# BlueBus.net
KiCad netlist of a schematic drawn in EAGLE
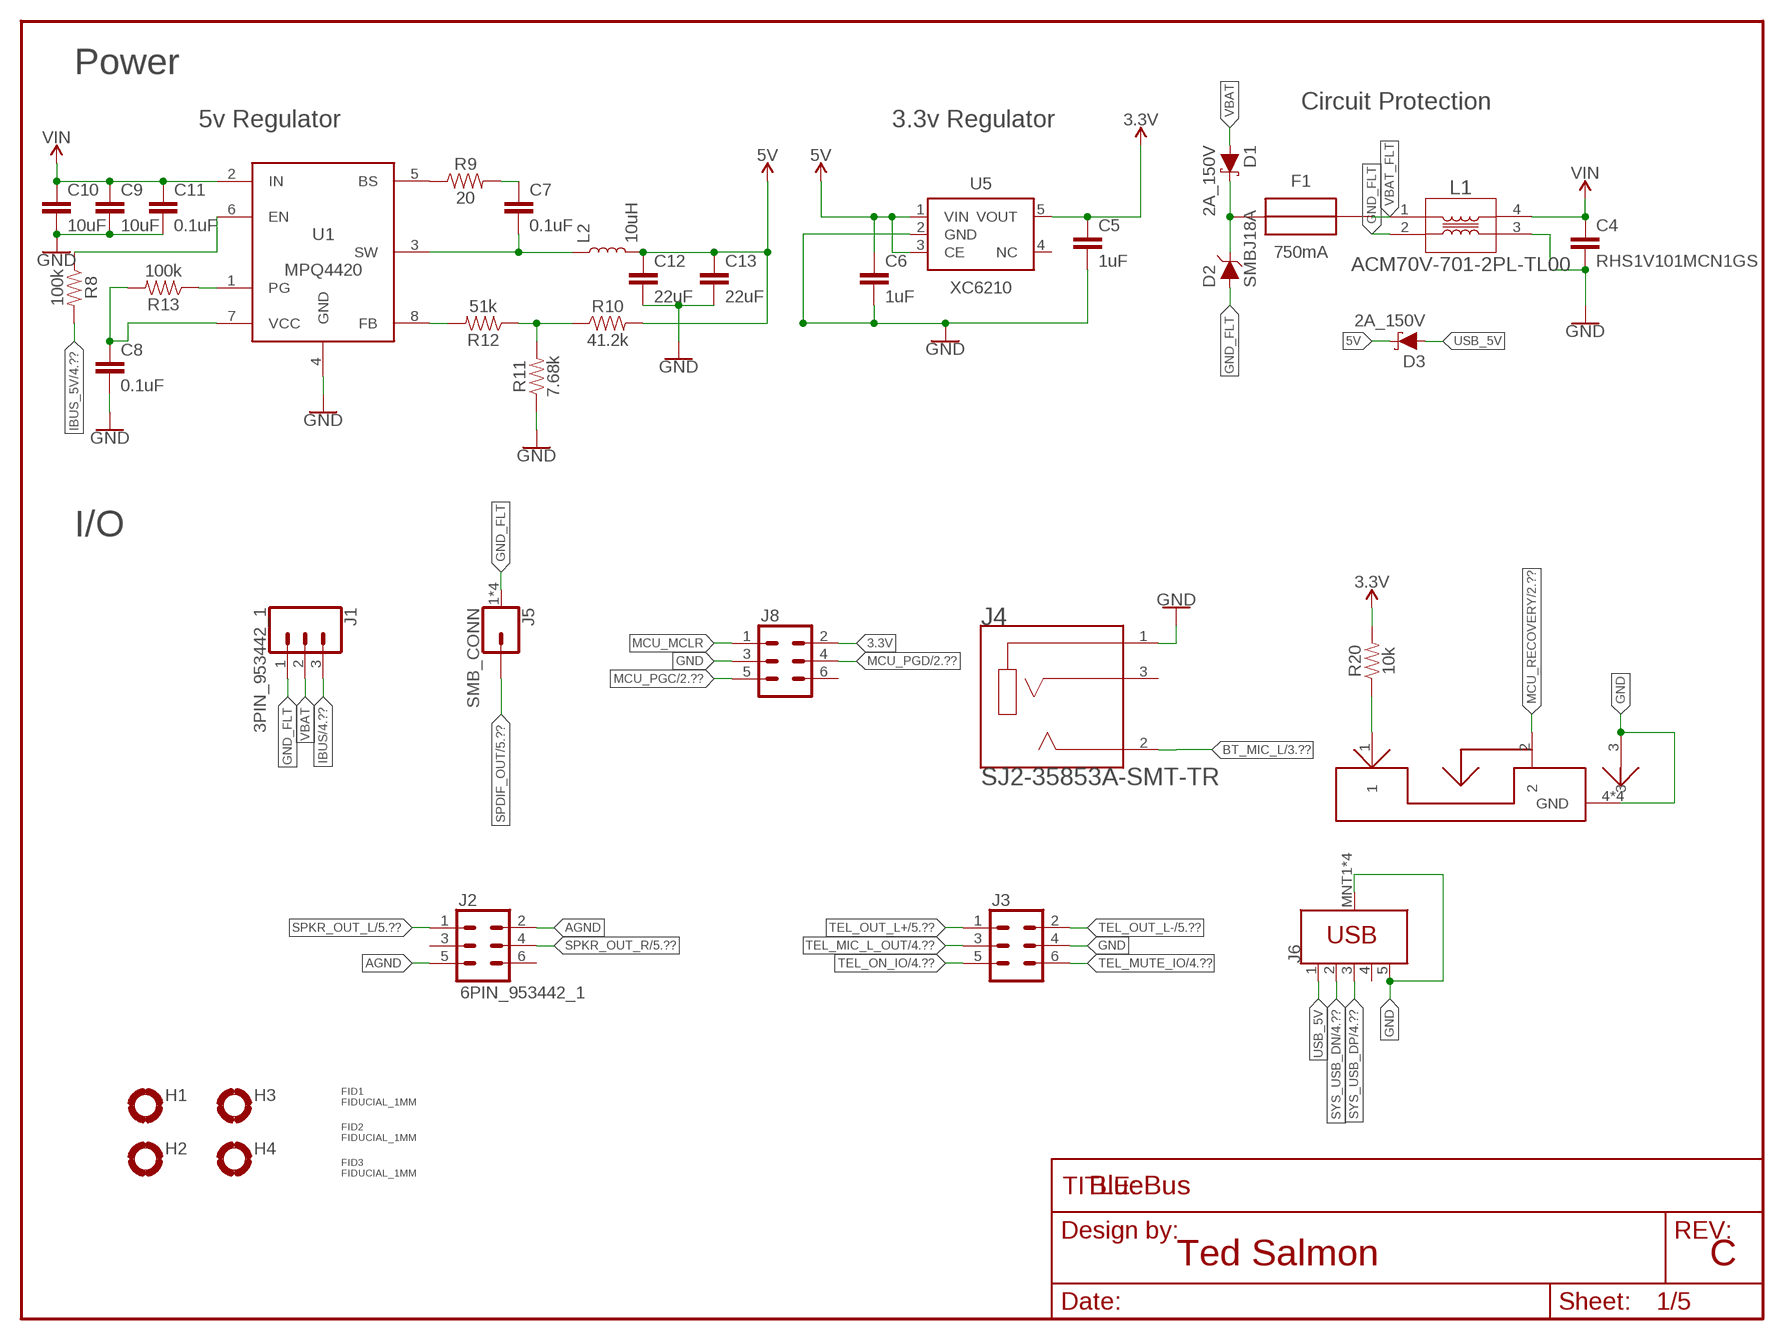
[diagram p0: schematic, sheet 1]
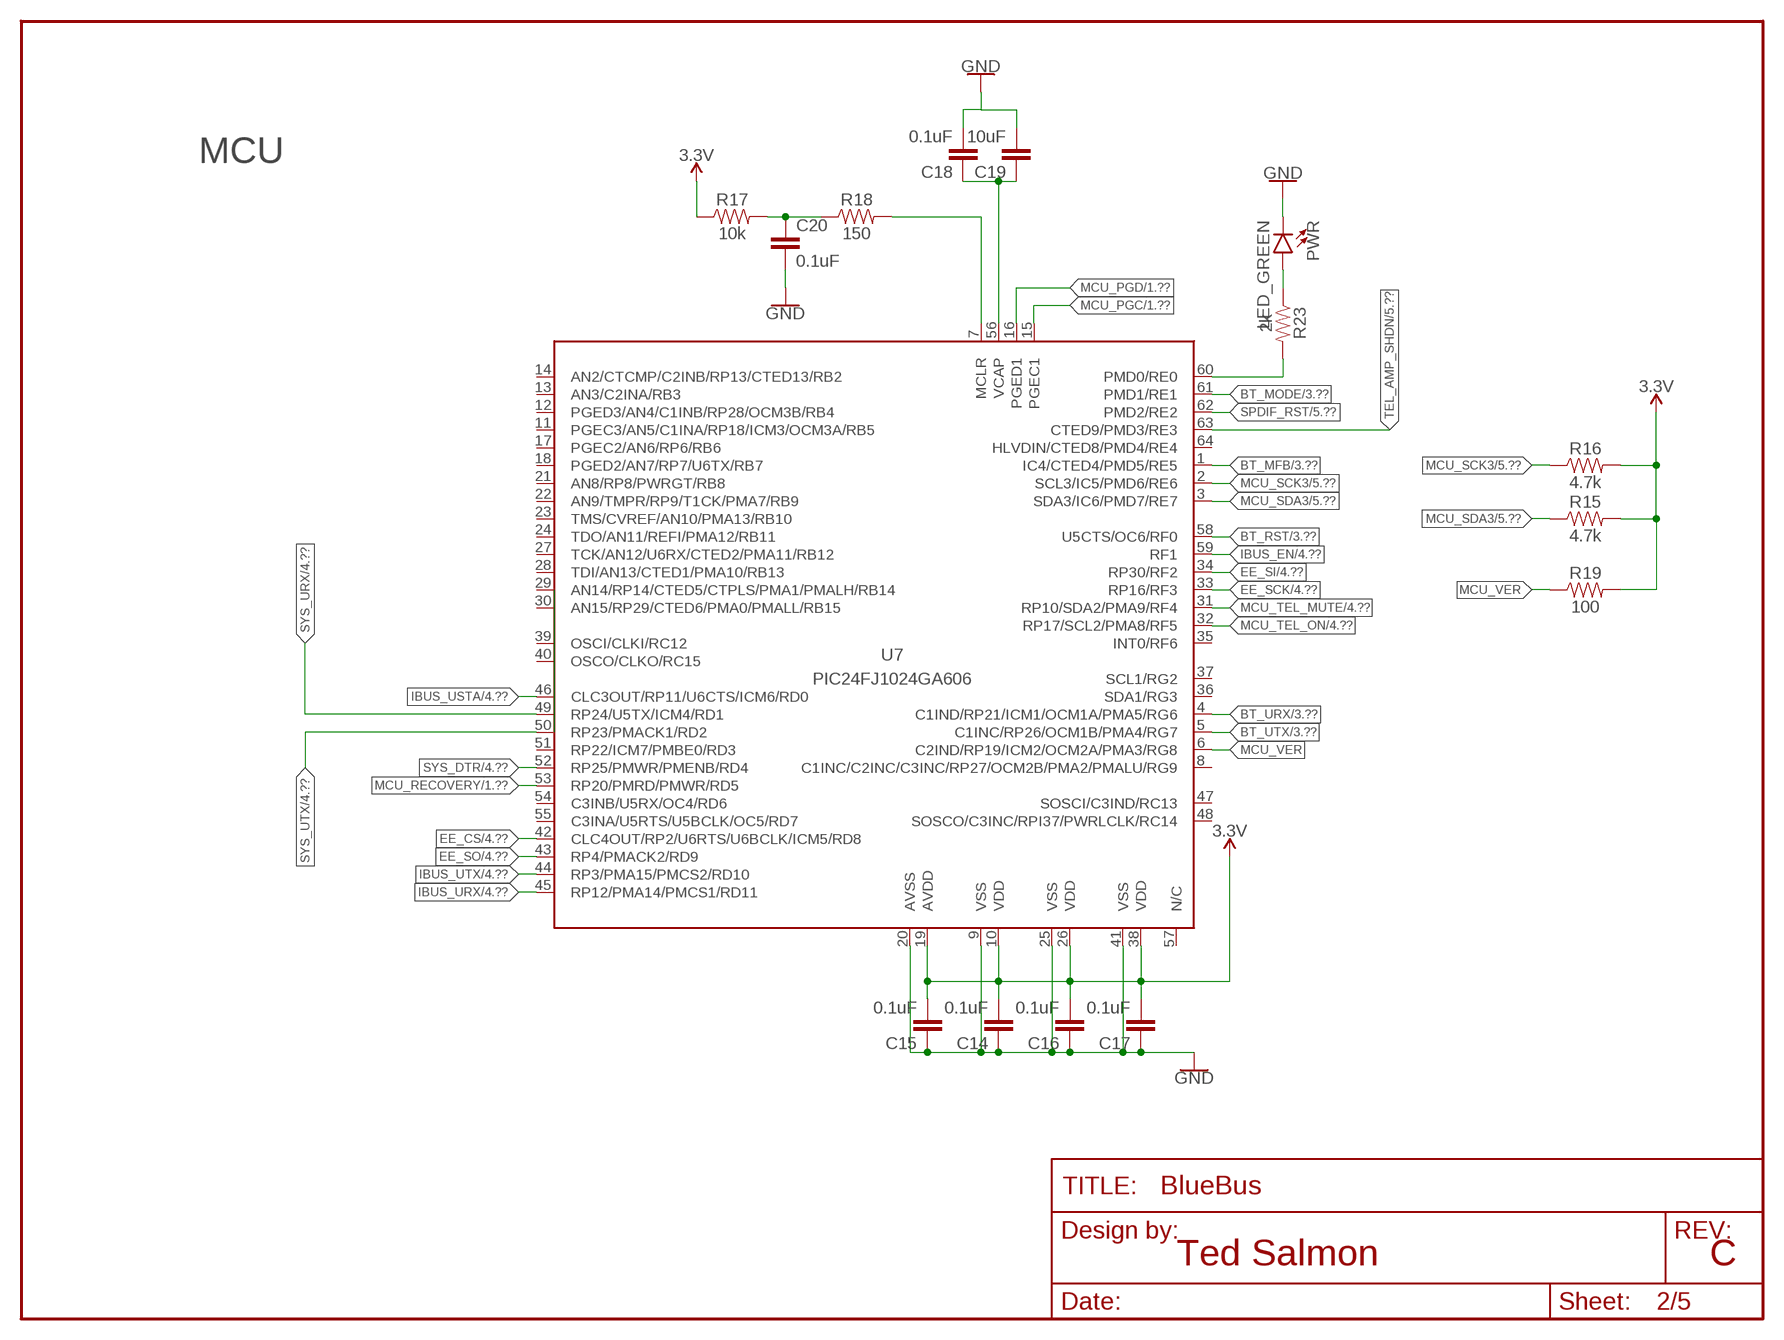
[diagram p1: schematic, sheet 2]
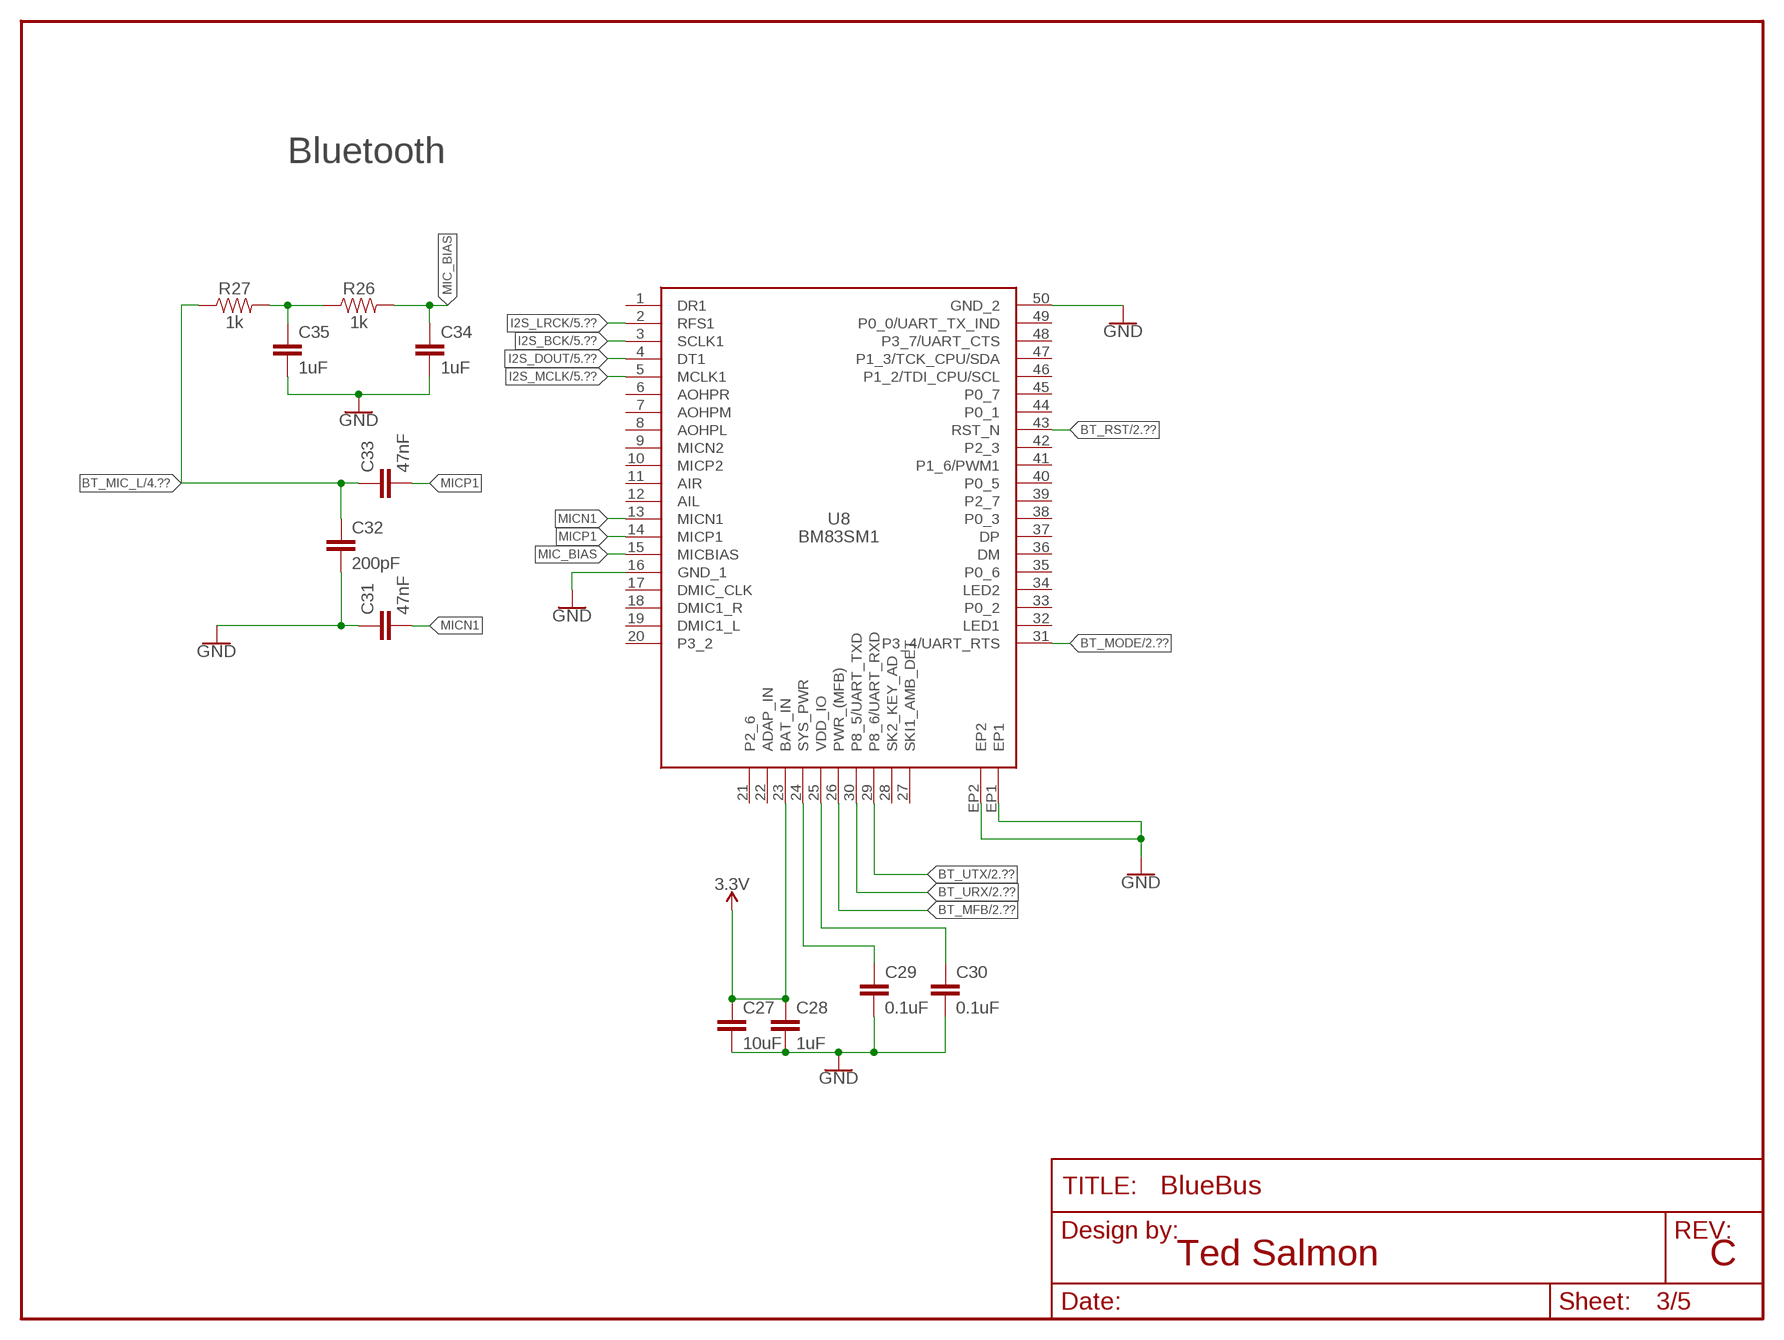
[diagram p2: schematic, sheet 3]
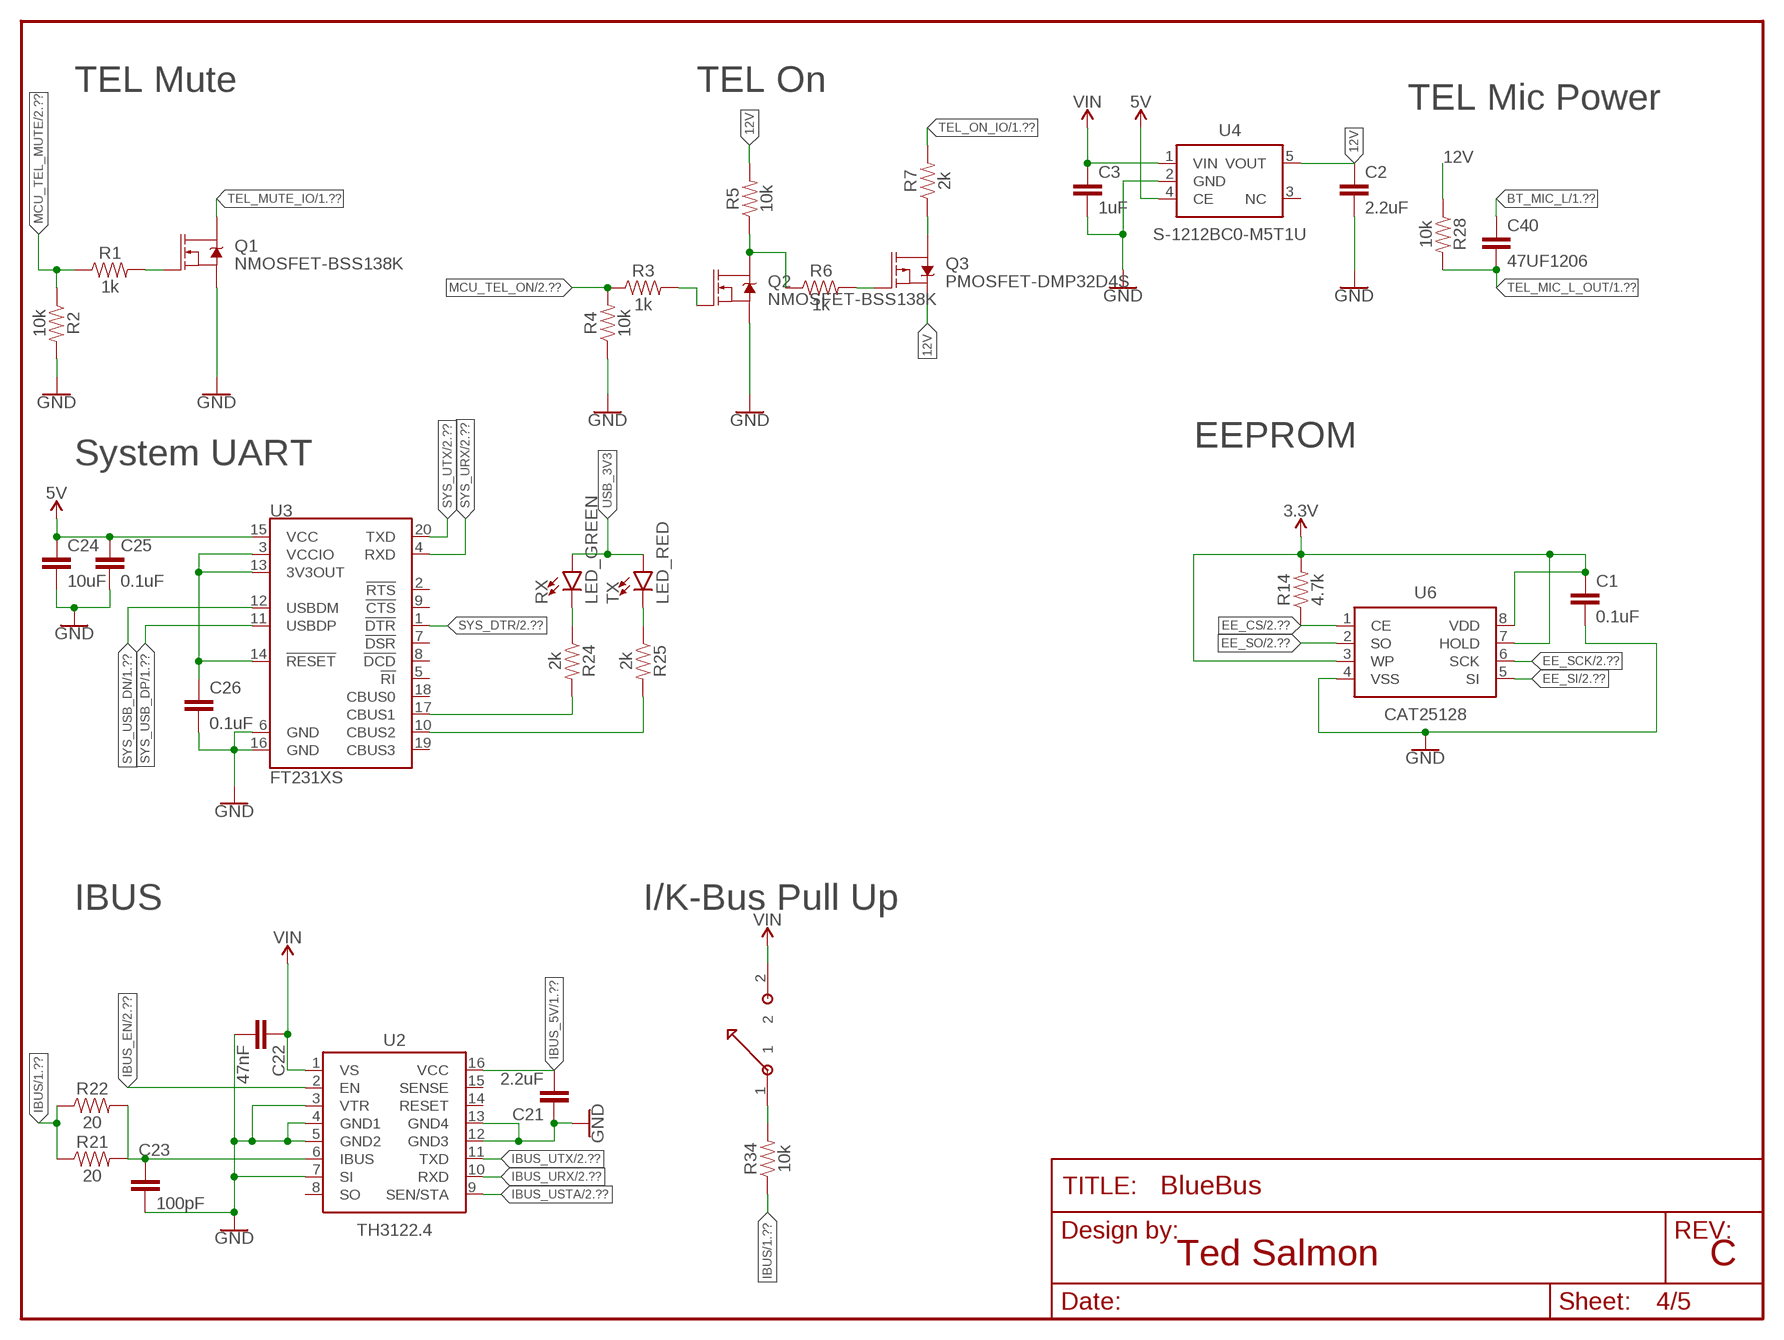
[diagram p3: schematic, sheet 4]
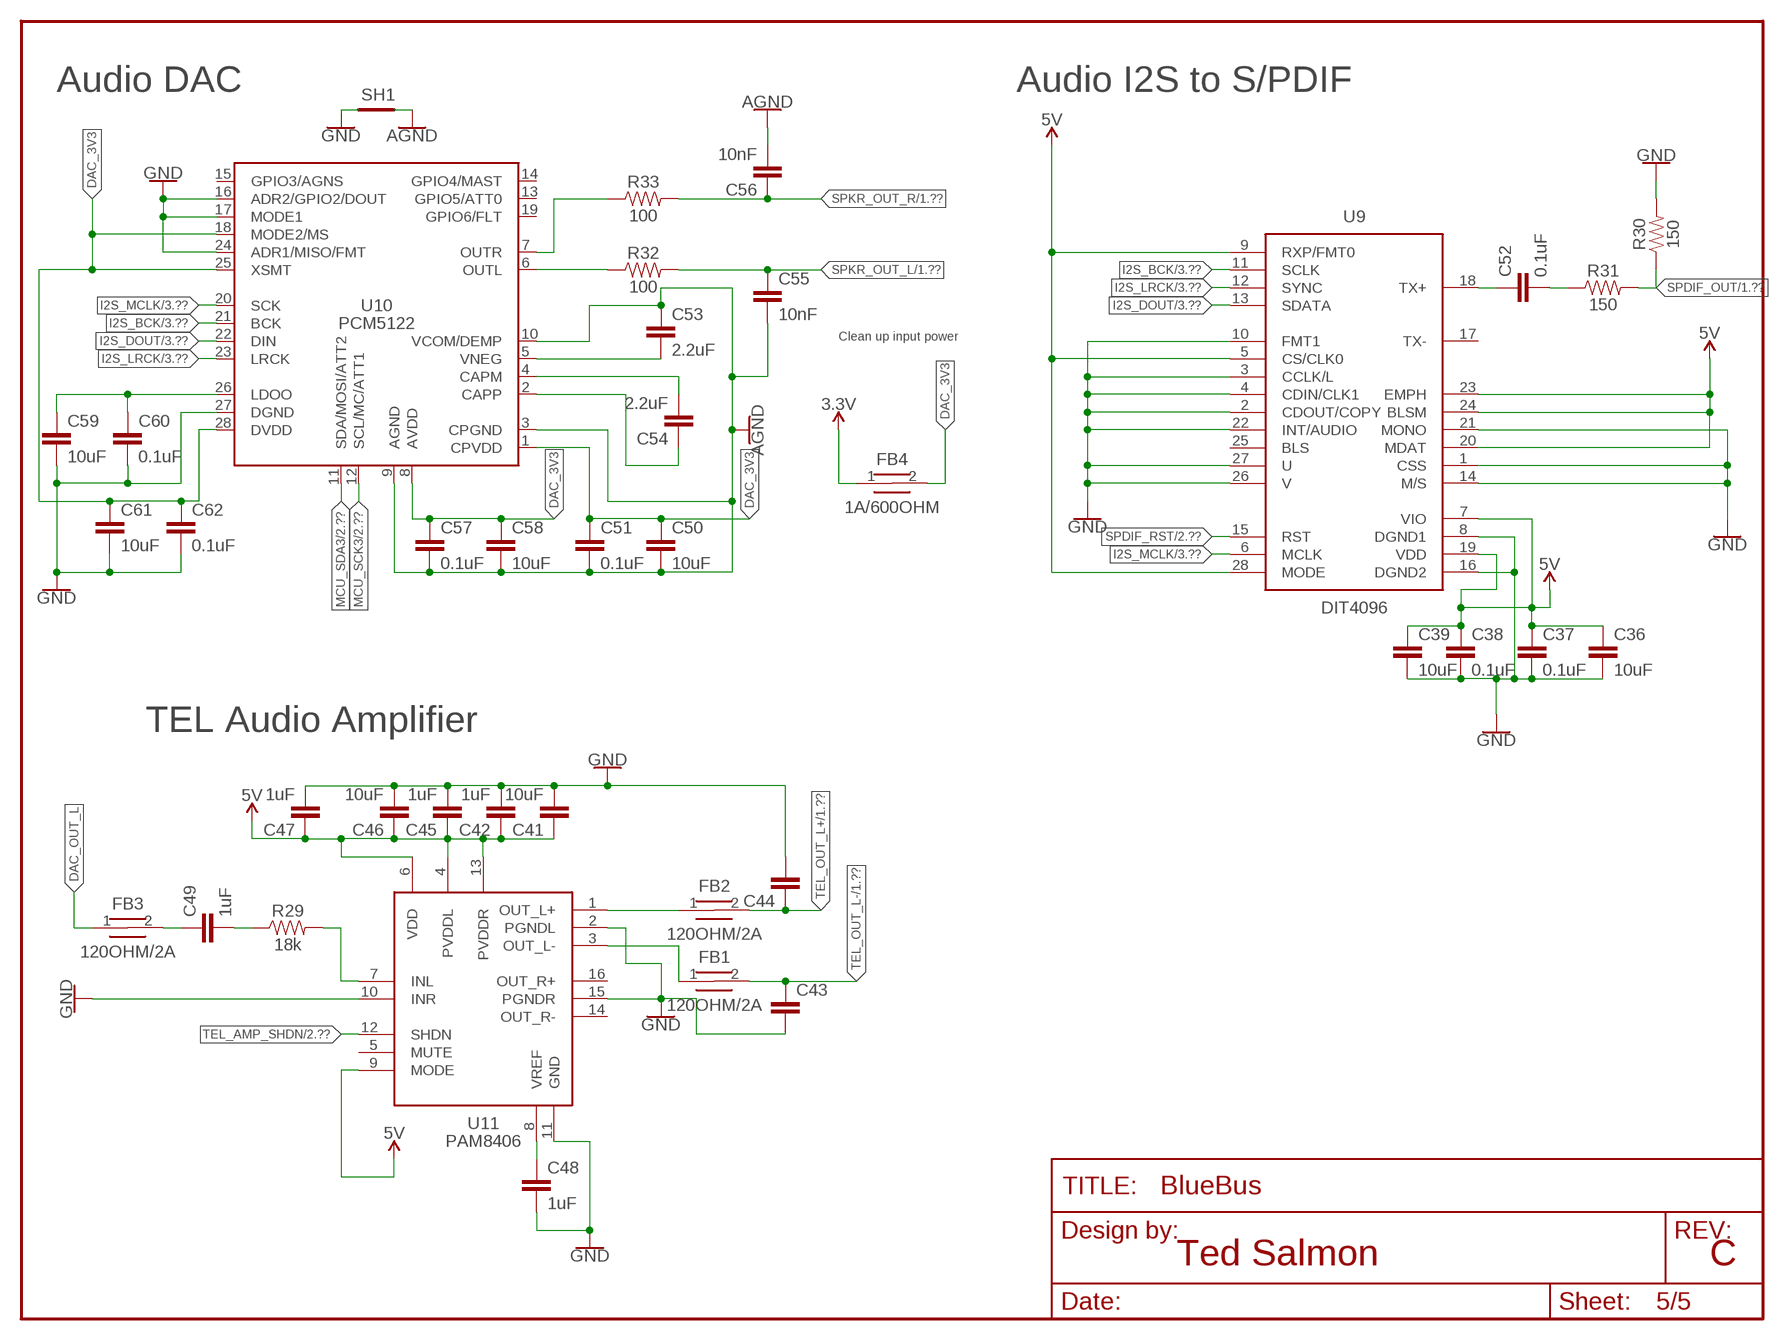
[diagram p4: schematic, sheet 5]

(export (version "E")
  (design (tool "Eeschema 10.0.6"))
  (components
    (comp (ref "C27")
      (value "10uF")
      (footprint "eagle-import:0603")
      (fields (field (name "MFG") "Murata"))
      (libsource (lib "eagle-import") (part "10UF0603"))
    )
    (comp (ref "C28")
      (value "1uF")
      (footprint "eagle-import:0603")
      (fields (field (name "MFG") "TDK"))
      (libsource (lib "eagle-import") (part "1UF0603"))
    )
    (comp (ref "C29")
      (value "0.1uF")
      (footprint "eagle-import:0603")
      (fields (field (name "MFG") "KEMET"))
      (libsource (lib "eagle-import") (part "0.1UF0603"))
    )
    (comp (ref "C30")
      (value "0.1uF")
      (footprint "eagle-import:0603")
      (fields (field (name "MFG") "KEMET"))
      (libsource (lib "eagle-import") (part "0.1UF0603"))
    )
    (comp (ref "C31")
      (value "47nF")
      (footprint "eagle-import:0603")
      (fields (field (name "MFG") "Kemet"))
      (libsource (lib "eagle-import") (part "47NF0603"))
    )
    (comp (ref "C32")
      (value "200pF")
      (footprint "eagle-import:0603")
      (fields (field (name "MFG") "Kemet"))
      (libsource (lib "eagle-import") (part "220PF0603"))
    )
    (comp (ref "C33")
      (value "47nF")
      (footprint "eagle-import:0603")
      (fields (field (name "MFG") "Kemet"))
      (libsource (lib "eagle-import") (part "47NF0603"))
    )
    (comp (ref "C34")
      (value "1uF")
      (footprint "eagle-import:0603")
      (fields (field (name "MFG") "TDK"))
      (libsource (lib "eagle-import") (part "1UF0603"))
    )
    (comp (ref "C35")
      (value "1uF")
      (footprint "eagle-import:0603")
      (fields (field (name "MFG") "TDK"))
      (libsource (lib "eagle-import") (part "1UF0603"))
    )
    (comp (ref "FRAME4")
      (value "FRAME-LETTER")
      (footprint "eagle-import:DUMMY")
      (libsource (lib "eagle-import") (part "FRAME-LETTER"))
    )
    (comp (ref "R26")
      (value "1k")
      (footprint "eagle-import:0603")
      (fields (field (name "MFG") "Panasonic"))
      (libsource (lib "eagle-import") (part "1KOHM0603"))
    )
    (comp (ref "R27")
      (value "1k")
      (footprint "eagle-import:0603")
      (fields (field (name "MFG") "Panasonic"))
      (libsource (lib "eagle-import") (part "1KOHM0603"))
    )
    (comp (ref "U8")
      (value "BM83SM1")
      (footprint "eagle-import:BM83SM1")
      (fields (field (name "MFG") "Microchip"))
      (libsource (lib "eagle-import") (part "BM83SM1"))
    )
    (comp (ref "C1")
      (value "0.1uF")
      (footprint "eagle-import:0603")
      (fields (field (name "MFG") "KEMET"))
      (libsource (lib "eagle-import") (part "0.1UF0603"))
    )
    (comp (ref "C2")
      (value "2.2uF")
      (footprint "eagle-import:0603")
      (fields (field (name "MFG") "KEMET"))
      (libsource (lib "eagle-import") (part "2.2UF0603"))
    )
    (comp (ref "C3")
      (value "1uF")
      (footprint "eagle-import:0603")
      (fields (field (name "MFG") "TDK"))
      (libsource (lib "eagle-import") (part "1UF0603"))
    )
    (comp (ref "C21")
      (value "2.2uF")
      (footprint "eagle-import:0603")
      (fields (field (name "MFG") "KEMET"))
      (libsource (lib "eagle-import") (part "2.2UF0603"))
    )
    (comp (ref "C22")
      (value "47nF")
      (footprint "eagle-import:0603")
      (fields (field (name "MFG") "Kemet"))
      (libsource (lib "eagle-import") (part "47NF0603"))
    )
    (comp (ref "C23")
      (value "100pF")
      (footprint "eagle-import:0603")
      (fields (field (name "MFG") "KEMET"))
      (libsource (lib "eagle-import") (part "100PF0603"))
    )
    (comp (ref "C24")
      (value "10uF")
      (footprint "eagle-import:0603")
      (fields (field (name "MFG") "Murata"))
      (libsource (lib "eagle-import") (part "10UF0603"))
    )
    (comp (ref "C25")
      (value "0.1uF")
      (footprint "eagle-import:0603")
      (fields (field (name "MFG") "KEMET"))
      (libsource (lib "eagle-import") (part "0.1UF0603"))
    )
    (comp (ref "C26")
      (value "0.1uF")
      (footprint "eagle-import:0603")
      (fields (field (name "MFG") "KEMET"))
      (libsource (lib "eagle-import") (part "0.1UF0603"))
    )
    (comp (ref "C40")
      (value "47UF1206")
      (footprint "eagle-import:1206")
      (fields (field (name "MFG") "MURATA"))
      (libsource (lib "eagle-import") (part "47UF1206"))
    )
    (comp (ref "FRAME3")
      (value "FRAME-LETTER")
      (footprint "eagle-import:DUMMY")
      (libsource (lib "eagle-import") (part "FRAME-LETTER"))
    )
    (comp (ref "Q1")
      (value "NMOSFET-BSS138K")
      (footprint "eagle-import:SOT-23")
      (fields (field (name "MFG") "Diodes"))
      (libsource (lib "eagle-import") (part "NMOSFET-BSS138K"))
    )
    (comp (ref "Q2")
      (value "NMOSFET-BSS138K")
      (footprint "eagle-import:SOT-23")
      (fields (field (name "MFG") "Diodes"))
      (libsource (lib "eagle-import") (part "NMOSFET-BSS138K"))
    )
    (comp (ref "Q3")
      (value "PMOSFET-DMP32D4S")
      (footprint "eagle-import:SOT-23")
      (fields (field (name "MFG") "Diodes"))
      (libsource (lib "eagle-import") (part "PMOSFET-DMP32D4S"))
    )
    (comp (ref "R1")
      (value "1k")
      (footprint "eagle-import:0603")
      (fields (field (name "MFG") "Panasonic"))
      (libsource (lib "eagle-import") (part "1KOHM0603"))
    )
    (comp (ref "R2")
      (value "10k")
      (footprint "eagle-import:0603")
      (fields (field (name "MFG") "Panasonic"))
      (libsource (lib "eagle-import") (part "10KOHM0603"))
    )
    (comp (ref "R3")
      (value "1k")
      (footprint "eagle-import:0603")
      (fields (field (name "MFG") "Panasonic"))
      (libsource (lib "eagle-import") (part "1KOHM0603"))
    )
    (comp (ref "R4")
      (value "10k")
      (footprint "eagle-import:0603")
      (fields (field (name "MFG") "Panasonic"))
      (libsource (lib "eagle-import") (part "10KOHM0603"))
    )
    (comp (ref "R5")
      (value "10k")
      (footprint "eagle-import:0603")
      (fields (field (name "MFG") "Panasonic"))
      (libsource (lib "eagle-import") (part "10KOHM0603"))
    )
    (comp (ref "R6")
      (value "1k")
      (footprint "eagle-import:0603")
      (fields (field (name "MFG") "Panasonic"))
      (libsource (lib "eagle-import") (part "1KOHM0603"))
    )
    (comp (ref "R7")
      (value "2k")
      (footprint "eagle-import:0603")
      (fields (field (name "MFG") "Panasonic"))
      (libsource (lib "eagle-import") (part "2KOHM0603"))
    )
    (comp (ref "R14")
      (value "4.7k")
      (footprint "eagle-import:0603")
      (fields (field (name "MFG") "Panasonic"))
      (libsource (lib "eagle-import") (part "4.7KOHM0603"))
    )
    (comp (ref "R21")
      (value "20")
      (footprint "eagle-import:0603")
      (fields (field (name "MFG") "Panasonic"))
      (libsource (lib "eagle-import") (part "20OHM0603"))
    )
    (comp (ref "R22")
      (value "20")
      (footprint "eagle-import:0603")
      (fields (field (name "MFG") "Panasonic"))
      (libsource (lib "eagle-import") (part "20OHM0603"))
    )
    (comp (ref "R24")
      (value "2k")
      (footprint "eagle-import:0603")
      (fields (field (name "MFG") "Panasonic"))
      (libsource (lib "eagle-import") (part "2KOHM0603"))
    )
    (comp (ref "R25")
      (value "2k")
      (footprint "eagle-import:0603")
      (fields (field (name "MFG") "Panasonic"))
      (libsource (lib "eagle-import") (part "2KOHM0603"))
    )
    (comp (ref "R28")
      (value "10k")
      (footprint "eagle-import:0603")
      (fields (field (name "MFG") "Panasonic"))
      (libsource (lib "eagle-import") (part "10KOHM0603"))
    )
    (comp (ref "R34")
      (value "10k")
      (footprint "eagle-import:0603")
      (fields (field (name "MFG") "Panasonic"))
      (libsource (lib "eagle-import") (part "10KOHM0603"))
    )
    (comp (ref "RX")
      (value "LED_GREEN")
      (footprint "eagle-import:LED-0805")
      (fields (field (name "MFG") "Wurth Elektronik"))
      (libsource (lib "eagle-import") (part "LED_GREEN"))
    )
    (comp (ref "SW1")
      (value "CHS-01TA1")
      (footprint "eagle-import:CHS-01TA1")
      (fields (field (name "MFG") "Nidec"))
      (libsource (lib "eagle-import") (part "CHS-01TA1"))
    )
    (comp (ref "TX")
      (value "LED_RED")
      (footprint "eagle-import:LED-0805")
      (fields (field (name "MFG") "Wurth Elektronik"))
      (libsource (lib "eagle-import") (part "LED_RED"))
    )
    (comp (ref "U2")
      (value "TH3122.4")
      (footprint "eagle-import:SOIC16DF")
      (fields (field (name "MFG") "Melexis"))
      (libsource (lib "eagle-import") (part "TH3122.4"))
    )
    (comp (ref "U3")
      (value "FT231XS")
      (footprint "eagle-import:SSOP20_L")
      (fields (field (name "MFG") "FTDI"))
      (libsource (lib "eagle-import") (part "FT231XS"))
    )
    (comp (ref "U4")
      (value "S-1212BC0-M5T1U")
      (footprint "eagle-import:SOT23-5")
      (fields (field (name "MFG") "Ablic"))
      (libsource (lib "eagle-import") (part "S-1212BC0M5T1"))
    )
    (comp (ref "U6")
      (value "CAT25128")
      (footprint "eagle-import:TSSOP-8")
      (fields (field (name "MFG") "ONSEMI"))
      (libsource (lib "eagle-import") (part "CAT25128"))
    )
    (comp (ref "C4")
      (value "RHS1V101MCN1GS")
      (footprint "eagle-import:RHS1V101MCN1GS")
      (fields (field (name "MFG") "Nichicon"))
      (libsource (lib "eagle-import") (part "RHS1V101MCN1GS"))
    )
    (comp (ref "C5")
      (value "1uF")
      (footprint "eagle-import:0603")
      (fields (field (name "MFG") "TDK"))
      (libsource (lib "eagle-import") (part "1UF0603"))
    )
    (comp (ref "C6")
      (value "1uF")
      (footprint "eagle-import:0603")
      (fields (field (name "MFG") "TDK"))
      (libsource (lib "eagle-import") (part "1UF0603"))
    )
    (comp (ref "C7")
      (value "0.1uF")
      (footprint "eagle-import:0603")
      (fields (field (name "MFG") "KEMET"))
      (libsource (lib "eagle-import") (part "0.1UF0603"))
    )
    (comp (ref "C8")
      (value "0.1uF")
      (footprint "eagle-import:0603")
      (fields (field (name "MFG") "KEMET"))
      (libsource (lib "eagle-import") (part "0.1UF0603"))
    )
    (comp (ref "C9")
      (value "10uF")
      (footprint "eagle-import:1206")
      (fields (field (name "MFG") "TDK"))
      (libsource (lib "eagle-import") (part "10UF"))
    )
    (comp (ref "C10")
      (value "10uF")
      (footprint "eagle-import:1206")
      (fields (field (name "MFG") "TDK"))
      (libsource (lib "eagle-import") (part "10UF"))
    )
    (comp (ref "C11")
      (value "0.1uF")
      (footprint "eagle-import:0603")
      (fields (field (name "MFG") "KEMET"))
      (libsource (lib "eagle-import") (part "0.1UF0603"))
    )
    (comp (ref "C12")
      (value "22uF")
      (footprint "eagle-import:0805")
      (fields (field (name "MFG") "TDK"))
      (libsource (lib "eagle-import") (part "22UF"))
    )
    (comp (ref "C13")
      (value "22uF")
      (footprint "eagle-import:0805")
      (fields (field (name "MFG") "TDK"))
      (libsource (lib "eagle-import") (part "22UF"))
    )
    (comp (ref "D1")
      (value "2A_150V")
      (footprint "eagle-import:SOD123FL-2")
      (fields (field (name "MFG") "MCC"))
      (libsource (lib "eagle-import") (part "SMD2150PL_2A_150V"))
    )
    (comp (ref "D2")
      (value "SMBJ18A")
      (footprint "eagle-import:DO-214AA")
      (fields (field (name "MFG") "Diodes"))
      (libsource (lib "eagle-import") (part "SMBJ18A"))
    )
    (comp (ref "D3")
      (value "2A_150V")
      (footprint "eagle-import:SOD123FL-2")
      (fields (field (name "MFG") "MCC"))
      (libsource (lib "eagle-import") (part "SMD2150PL_2A_150V"))
    )
    (comp (ref "F1")
      (value "750mA")
      (footprint "eagle-import:LITTLEFUSE")
      (fields (field (name "MFG") "Littelfuse"))
      (libsource (lib "eagle-import") (part "LITTLEBLOCK_FUSE_.75A"))
    )
    (comp (ref "FID1")
      (value "FIDUCIAL_1MM")
      (footprint "eagle-import:FIDUCIAL_1MM")
      (libsource (lib "eagle-import") (part "FIDUCIAL_1MM"))
    )
    (comp (ref "FID2")
      (value "FIDUCIAL_1MM")
      (footprint "eagle-import:FIDUCIAL_1MM")
      (libsource (lib "eagle-import") (part "FIDUCIAL_1MM"))
    )
    (comp (ref "FID3")
      (value "FIDUCIAL_1MM")
      (footprint "eagle-import:FIDUCIAL_1MM")
      (libsource (lib "eagle-import") (part "FIDUCIAL_1MM"))
    )
    (comp (ref "FRAME1")
      (value "FRAME-LETTER")
      (footprint "eagle-import:DUMMY")
      (libsource (lib "eagle-import") (part "FRAME-LETTER"))
    )
    (comp (ref "H1")
      (value "2,5-HOLE")
      (footprint "eagle-import:2.5-HOLE")
      (libsource (lib "eagle-import") (part "2,5-HOLE"))
    )
    (comp (ref "H2")
      (value "2,5-HOLE")
      (footprint "eagle-import:2.5-HOLE")
      (libsource (lib "eagle-import") (part "2,5-HOLE"))
    )
    (comp (ref "H3")
      (value "2,5-HOLE")
      (footprint "eagle-import:2.5-HOLE")
      (libsource (lib "eagle-import") (part "2,5-HOLE"))
    )
    (comp (ref "H4")
      (value "2,5-HOLE")
      (footprint "eagle-import:2.5-HOLE")
      (libsource (lib "eagle-import") (part "2,5-HOLE"))
    )
    (comp (ref "J1")
      (value "3PIN_953442_1")
      (footprint "eagle-import:TE_MQS_3PIN")
      (libsource (lib "eagle-import") (part "3PIN_953442_1"))
    )
    (comp (ref "J2")
      (value "6PIN_953442_1")
      (footprint "eagle-import:TE_MQS_6PIN")
      (fields (field (name "MFG") "TE"))
      (libsource (lib "eagle-import") (part "6PIN_953442_1"))
    )
    (comp (ref "J3")
      (value "6PIN_5_103166_1")
      (footprint "eagle-import:TE_AMPMODU_6_PIN")
      (fields (field (name "MFG") "TE"))
      (libsource (lib "eagle-import") (part "6PIN_5_103166_1"))
    )
    (comp (ref "J4")
      (value "SJ2-35853A-SMT-TR")
      (footprint "eagle-import:CUI_SJ2_35853A_SMT_TR")
      (fields (field (name "MFG") "CUI"))
      (libsource (lib "eagle-import") (part "SJ2-35853A-SMT-TR"))
    )
    (comp (ref "J5")
      (value "SMB_CONN")
      (footprint "eagle-import:MOLEX_SMB")
      (fields (field (name "MFG") "Molex"))
      (libsource (lib "eagle-import") (part "SMB_CONN"))
    )
    (comp (ref "J6")
      (value "USB3080-30-01-A")
      (footprint "eagle-import:USB3080-30-01-A")
      (fields (field (name "MFG") "Global Connector Technology"))
      (libsource (lib "eagle-import") (part "USB3080-30-01-A"))
    )
    (comp (ref "J7")
      (value "PCM12SMTR")
      (footprint "eagle-import:PCM12SMTR")
      (libsource (lib "eagle-import") (part "PCM12SMTR"))
    )
    (comp (ref "J8")
      (value "TC2030NL")
      (footprint "eagle-import:TC2030-NL")
      (libsource (lib "eagle-import") (part "TC2030NL"))
    )
    (comp (ref "L1")
      (value "ACM70V-701-2PL-TL00")
      (footprint "eagle-import:ACM70V-701-2PL-TL00")
      (fields (field (name "MFG") "TDK"))
      (libsource (lib "eagle-import") (part "ACM70V-701-2PL-TL00"))
    )
    (comp (ref "L2")
      (value "10uH")
      (footprint "eagle-import:MPL-SE5040")
      (fields (field (name "MFG") "Monolithic Power Systems"))
      (libsource (lib "eagle-import") (part "MPL-SE5040-100"))
    )
    (comp (ref "R8")
      (value "100k")
      (footprint "eagle-import:0603")
      (fields (field (name "MFG") "Panasonic"))
      (libsource (lib "eagle-import") (part "100KOHM0603"))
    )
    (comp (ref "R9")
      (value "20")
      (footprint "eagle-import:0603")
      (fields (field (name "MFG") "Panasonic"))
      (libsource (lib "eagle-import") (part "20OHM0603"))
    )
    (comp (ref "R10")
      (value "41.2k")
      (footprint "eagle-import:0603")
      (fields (field (name "MFG") "Panasonic"))
      (libsource (lib "eagle-import") (part "41.2KOHM0603"))
    )
    (comp (ref "R11")
      (value "7.68k")
      (footprint "eagle-import:0603")
      (fields (field (name "MFG") "Panasonic"))
      (libsource (lib "eagle-import") (part "7.68KOHM0603"))
    )
    (comp (ref "R12")
      (value "51k")
      (footprint "eagle-import:0603")
      (fields (field (name "MFG") "Panasonic"))
      (libsource (lib "eagle-import") (part "51KOHM0603"))
    )
    (comp (ref "R13")
      (value "100k")
      (footprint "eagle-import:0603")
      (fields (field (name "MFG") "Panasonic"))
      (libsource (lib "eagle-import") (part "100KOHM0603"))
    )
    (comp (ref "R20")
      (value "10k")
      (footprint "eagle-import:0603")
      (fields (field (name "MFG") "Panasonic"))
      (libsource (lib "eagle-import") (part "10KOHM0603"))
    )
    (comp (ref "U1")
      (value "MPQ4420")
      (footprint "eagle-import:TSOT23-8")
      (fields (field (name "MFG") "Monolithic Power Systems"))
      (libsource (lib "eagle-import") (part "MPQ4420"))
    )
    (comp (ref "U5")
      (value "XC6210")
      (footprint "eagle-import:SOT23-5")
      (fields (field (name "MFG") "Torex"))
      (libsource (lib "eagle-import") (part "XC6210SOT25"))
    )
    (comp (ref "C14")
      (value "0.1uF")
      (footprint "eagle-import:0603")
      (fields (field (name "MFG") "KEMET"))
      (libsource (lib "eagle-import") (part "0.1UF0603"))
    )
    (comp (ref "C15")
      (value "0.1uF")
      (footprint "eagle-import:0603")
      (fields (field (name "MFG") "KEMET"))
      (libsource (lib "eagle-import") (part "0.1UF0603"))
    )
    (comp (ref "C16")
      (value "0.1uF")
      (footprint "eagle-import:0603")
      (fields (field (name "MFG") "KEMET"))
      (libsource (lib "eagle-import") (part "0.1UF0603"))
    )
    (comp (ref "C17")
      (value "0.1uF")
      (footprint "eagle-import:0603")
      (fields (field (name "MFG") "KEMET"))
      (libsource (lib "eagle-import") (part "0.1UF0603"))
    )
    (comp (ref "C18")
      (value "0.1uF")
      (footprint "eagle-import:0603")
      (fields (field (name "MFG") "KEMET"))
      (libsource (lib "eagle-import") (part "0.1UF0603"))
    )
    (comp (ref "C19")
      (value "10uF")
      (footprint "eagle-import:0603")
      (fields (field (name "MFG") "Murata"))
      (libsource (lib "eagle-import") (part "10UF0603"))
    )
    (comp (ref "C20")
      (value "0.1uF")
      (footprint "eagle-import:0603")
      (fields (field (name "MFG") "KEMET"))
      (libsource (lib "eagle-import") (part "0.1UF0603"))
    )
    (comp (ref "FRAME2")
      (value "FRAME-LETTER")
      (footprint "eagle-import:DUMMY")
      (libsource (lib "eagle-import") (part "FRAME-LETTER"))
    )
    (comp (ref "PWR")
      (value "LED_GREEN")
      (footprint "eagle-import:LED-0805")
      (fields (field (name "MFG") "Wurth Elektronik"))
      (libsource (lib "eagle-import") (part "LED_GREEN"))
    )
    (comp (ref "R15")
      (value "4.7k")
      (footprint "eagle-import:0603")
      (fields (field (name "MFG") "Panasonic"))
      (libsource (lib "eagle-import") (part "4.7KOHM0603"))
    )
    (comp (ref "R16")
      (value "4.7k")
      (footprint "eagle-import:0603")
      (fields (field (name "MFG") "Panasonic"))
      (libsource (lib "eagle-import") (part "4.7KOHM0603"))
    )
    (comp (ref "R17")
      (value "10k")
      (footprint "eagle-import:0603")
      (fields (field (name "MFG") "Panasonic"))
      (libsource (lib "eagle-import") (part "10KOHM0603"))
    )
    (comp (ref "R18")
      (value "150")
      (footprint "eagle-import:0603")
      (fields (field (name "MFG") "Panasonic"))
      (libsource (lib "eagle-import") (part "150OHM0603"))
    )
    (comp (ref "R19")
      (value "100")
      (footprint "eagle-import:0603")
      (fields (field (name "MFG") "Panasonic"))
      (libsource (lib "eagle-import") (part "100OHM0603"))
    )
    (comp (ref "R23")
      (value "2k")
      (footprint "eagle-import:0603")
      (fields (field (name "MFG") "Panasonic"))
      (libsource (lib "eagle-import") (part "2KOHM0603"))
    )
    (comp (ref "U7")
      (value "PIC24FJ1024GA606")
      (footprint "eagle-import:TQFP64")
      (fields (field (name "MFG") "Microchip"))
      (libsource (lib "eagle-import") (part "PIC24FJ1024GA606"))
    )
    (comp (ref "C36")
      (value "10uF")
      (footprint "eagle-import:0603")
      (fields (field (name "MFG") "Murata"))
      (libsource (lib "eagle-import") (part "10UF0603"))
    )
    (comp (ref "C37")
      (value "0.1uF")
      (footprint "eagle-import:0603")
      (fields (field (name "MFG") "KEMET"))
      (libsource (lib "eagle-import") (part "0.1UF0603"))
    )
    (comp (ref "C38")
      (value "0.1uF")
      (footprint "eagle-import:0603")
      (fields (field (name "MFG") "KEMET"))
      (libsource (lib "eagle-import") (part "0.1UF0603"))
    )
    (comp (ref "C39")
      (value "10uF")
      (footprint "eagle-import:0603")
      (fields (field (name "MFG") "Murata"))
      (libsource (lib "eagle-import") (part "10UF0603"))
    )
    (comp (ref "C41")
      (value "10uF")
      (footprint "eagle-import:0603")
      (fields (field (name "MFG") "Murata"))
      (libsource (lib "eagle-import") (part "10UF0603"))
    )
    (comp (ref "C42")
      (value "1uF")
      (footprint "eagle-import:0603")
      (fields (field (name "MFG") "TDK"))
      (libsource (lib "eagle-import") (part "1UF0603"))
    )
    (comp (ref "C43")
      (value "200pF")
      (footprint "eagle-import:0603")
      (fields (field (name "MFG") "Kemet"))
      (libsource (lib "eagle-import") (part "220PF0603"))
    )
    (comp (ref "C44")
      (value "200pF")
      (footprint "eagle-import:0603")
      (fields (field (name "MFG") "Kemet"))
      (libsource (lib "eagle-import") (part "220PF0603"))
    )
    (comp (ref "C45")
      (value "1uF")
      (footprint "eagle-import:0603")
      (fields (field (name "MFG") "TDK"))
      (libsource (lib "eagle-import") (part "1UF0603"))
    )
    (comp (ref "C46")
      (value "10uF")
      (footprint "eagle-import:0603")
      (fields (field (name "MFG") "Murata"))
      (libsource (lib "eagle-import") (part "10UF0603"))
    )
    (comp (ref "C47")
      (value "1uF")
      (footprint "eagle-import:0603")
      (fields (field (name "MFG") "TDK"))
      (libsource (lib "eagle-import") (part "1UF0603"))
    )
    (comp (ref "C48")
      (value "1uF")
      (footprint "eagle-import:0603")
      (fields (field (name "MFG") "TDK"))
      (libsource (lib "eagle-import") (part "1UF0603"))
    )
    (comp (ref "C49")
      (value "1uF")
      (footprint "eagle-import:0603")
      (fields (field (name "MFG") "TDK"))
      (libsource (lib "eagle-import") (part "1UF0603"))
    )
    (comp (ref "C50")
      (value "10uF")
      (footprint "eagle-import:0603")
      (fields (field (name "MFG") "Murata"))
      (libsource (lib "eagle-import") (part "10UF0603"))
    )
    (comp (ref "C51")
      (value "0.1uF")
      (footprint "eagle-import:0603")
      (fields (field (name "MFG") "KEMET"))
      (libsource (lib "eagle-import") (part "0.1UF0603"))
    )
    (comp (ref "C52")
      (value "0.1uF")
      (footprint "eagle-import:0603")
      (fields (field (name "MFG") "KEMET"))
      (libsource (lib "eagle-import") (part "0.1UF0603"))
    )
    (comp (ref "C53")
      (value "2.2uF")
      (footprint "eagle-import:0603")
      (fields (field (name "MFG") "KEMET"))
      (libsource (lib "eagle-import") (part "2.2UF0603"))
    )
    (comp (ref "C54")
      (value "2.2uF")
      (footprint "eagle-import:0603")
      (fields (field (name "MFG") "KEMET"))
      (libsource (lib "eagle-import") (part "2.2UF0603"))
    )
    (comp (ref "C55")
      (value "10nF")
      (footprint "eagle-import:0603")
      (fields (field (name "MFG") "KEMET"))
      (libsource (lib "eagle-import") (part "10NF0603"))
    )
    (comp (ref "C56")
      (value "10nF")
      (footprint "eagle-import:0603")
      (fields (field (name "MFG") "KEMET"))
      (libsource (lib "eagle-import") (part "10NF0603"))
    )
    (comp (ref "C57")
      (value "0.1uF")
      (footprint "eagle-import:0603")
      (fields (field (name "MFG") "KEMET"))
      (libsource (lib "eagle-import") (part "0.1UF0603"))
    )
    (comp (ref "C58")
      (value "10uF")
      (footprint "eagle-import:0603")
      (fields (field (name "MFG") "Murata"))
      (libsource (lib "eagle-import") (part "10UF0603"))
    )
    (comp (ref "C59")
      (value "10uF")
      (footprint "eagle-import:0603")
      (fields (field (name "MFG") "Murata"))
      (libsource (lib "eagle-import") (part "10UF0603"))
    )
    (comp (ref "C60")
      (value "0.1uF")
      (footprint "eagle-import:0603")
      (fields (field (name "MFG") "KEMET"))
      (libsource (lib "eagle-import") (part "0.1UF0603"))
    )
    (comp (ref "C61")
      (value "10uF")
      (footprint "eagle-import:0603")
      (fields (field (name "MFG") "Murata"))
      (libsource (lib "eagle-import") (part "10UF0603"))
    )
    (comp (ref "C62")
      (value "0.1uF")
      (footprint "eagle-import:0603")
      (fields (field (name "MFG") "KEMET"))
      (libsource (lib "eagle-import") (part "0.1UF0603"))
    )
    (comp (ref "FB1")
      (value "120OHM/2A")
      (footprint "eagle-import:0603")
      (fields (field (name "MFG") "Bourns"))
      (libsource (lib "eagle-import") (part "FERRITE_2A/120OHM0603"))
    )
    (comp (ref "FB2")
      (value "120OHM/2A")
      (footprint "eagle-import:0603")
      (fields (field (name "MFG") "Bourns"))
      (libsource (lib "eagle-import") (part "FERRITE_2A/120OHM0603"))
    )
    (comp (ref "FB3")
      (value "120OHM/2A")
      (footprint "eagle-import:0603")
      (fields (field (name "MFG") "Bourns"))
      (libsource (lib "eagle-import") (part "FERRITE_2A/120OHM0603"))
    )
    (comp (ref "FB4")
      (value "1A/600OHM")
      (footprint "eagle-import:0603")
      (fields (field (name "MFG") "Murata"))
      (libsource (lib "eagle-import") (part "FERRITE_1A/600OHM"))
    )
    (comp (ref "FRAME5")
      (value "FRAME-LETTER")
      (footprint "eagle-import:DUMMY")
      (libsource (lib "eagle-import") (part "FRAME-LETTER"))
    )
    (comp (ref "R29")
      (value "18k")
      (footprint "eagle-import:0603")
      (fields (field (name "MFG") "Panasonic"))
      (libsource (lib "eagle-import") (part "18KOHM0603"))
    )
    (comp (ref "R30")
      (value "150")
      (footprint "eagle-import:0603")
      (fields (field (name "MFG") "Panasonic"))
      (libsource (lib "eagle-import") (part "150OHM0603"))
    )
    (comp (ref "R31")
      (value "150")
      (footprint "eagle-import:0603")
      (fields (field (name "MFG") "Panasonic"))
      (libsource (lib "eagle-import") (part "150OHM0603"))
    )
    (comp (ref "R32")
      (value "100")
      (footprint "eagle-import:0603")
      (fields (field (name "MFG") "Panasonic"))
      (libsource (lib "eagle-import") (part "100OHM0603"))
    )
    (comp (ref "R33")
      (value "100")
      (footprint "eagle-import:0603")
      (fields (field (name "MFG") "Panasonic"))
      (libsource (lib "eagle-import") (part "100OHM0603"))
    )
    (comp (ref "SH1")
      (value "SHORTT5")
      (footprint "eagle-import:SHORT_TOP-50")
      (libsource (lib "eagle-import") (part "SHORTT5"))
    )
    (comp (ref "U9")
      (value "DIT4096")
      (footprint "eagle-import:TSSOP28")
      (fields (field (name "MFG") "Texas Instruments"))
      (libsource (lib "eagle-import") (part "DIT4096"))
    )
    (comp (ref "U10")
      (value "PCM5122")
      (footprint "eagle-import:TSSOP28")
      (fields (field (name "MFG") "Texas Instruments"))
      (libsource (lib "eagle-import") (part "PCM5122"))
    )
    (comp (ref "U11")
      (value "PAM8406")
      (footprint "eagle-import:SOP-16")
      (fields (field (name "MFG") "Diodes"))
      (libsource (lib "eagle-import") (part "PAM8406"))
    )
  )
  (nets
    (net (code "1") (name "3.3V") (class "Default")
      (node (ref "C1") (pin "1") (pinfunction "1_1") (pintype "passive"))
      (node (ref "C14") (pin "2") (pinfunction "2_2") (pintype "passive"))
      (node (ref "C15") (pin "2") (pinfunction "2_2") (pintype "passive"))
      (node (ref "C16") (pin "2") (pinfunction "2_2") (pintype "passive"))
      (node (ref "C17") (pin "2") (pinfunction "2_2") (pintype "passive"))
      (node (ref "C27") (pin "1") (pinfunction "1_1") (pintype "passive"))
      (node (ref "C28") (pin "1") (pinfunction "1_1") (pintype "passive"))
      (node (ref "C5") (pin "1") (pinfunction "1_1") (pintype "passive"))
      (node (ref "FB4") (pin "1") (pinfunction "1_1") (pintype "bidirectional"))
      (node (ref "J8") (pin "2") (pinfunction "2_2") (pintype "bidirectional"))
      (node (ref "R14") (pin "2") (pinfunction "2_2") (pintype "passive"))
      (node (ref "R15") (pin "2") (pinfunction "2_2") (pintype "passive"))
      (node (ref "R16") (pin "2") (pinfunction "2_2") (pintype "passive"))
      (node (ref "R17") (pin "1") (pinfunction "1_1") (pintype "passive"))
      (node (ref "R19") (pin "2") (pinfunction "2_2") (pintype "passive"))
      (node (ref "R20") (pin "2") (pinfunction "2_2") (pintype "passive"))
      (node (ref "U5") (pin "5") (pinfunction "VOUT_5") (pintype "power_in"))
      (node (ref "U6") (pin "3") (pinfunction "WP_3") (pintype "bidirectional"))
      (node (ref "U6") (pin "7") (pinfunction "HOLD_7") (pintype "bidirectional"))
      (node (ref "U6") (pin "8") (pinfunction "VDD_8") (pintype "power_in"))
      (node (ref "U7") (pin "10") (pinfunction "VDD_10") (pintype "power_in"))
      (node (ref "U7") (pin "19") (pinfunction "AVDD_19") (pintype "power_in"))
      (node (ref "U7") (pin "26") (pinfunction "VDD_26") (pintype "power_in"))
      (node (ref "U7") (pin "38") (pinfunction "VDD_38") (pintype "power_in"))
      (node (ref "U8") (pin "23") (pinfunction "BAT_IN_23") (pintype "bidirectional"))
    )
    (net (code "2") (name "5V") (class "Default")
      (node (ref "C12") (pin "1") (pinfunction "1_1") (pintype "passive"))
      (node (ref "C13") (pin "1") (pinfunction "1_1") (pintype "passive"))
      (node (ref "C24") (pin "1") (pinfunction "1_1") (pintype "passive"))
      (node (ref "C25") (pin "1") (pinfunction "1_1") (pintype "passive"))
      (node (ref "C36") (pin "1") (pinfunction "1_1") (pintype "passive"))
      (node (ref "C37") (pin "1") (pinfunction "1_1") (pintype "passive"))
      (node (ref "C38") (pin "1") (pinfunction "1_1") (pintype "passive"))
      (node (ref "C39") (pin "1") (pinfunction "1_1") (pintype "passive"))
      (node (ref "C41") (pin "1") (pinfunction "1_1") (pintype "passive"))
      (node (ref "C42") (pin "1") (pinfunction "1_1") (pintype "passive"))
      (node (ref "C45") (pin "1") (pinfunction "1_1") (pintype "passive"))
      (node (ref "C46") (pin "1") (pinfunction "1_1") (pintype "passive"))
      (node (ref "C47") (pin "1") (pinfunction "1_1") (pintype "passive"))
      (node (ref "C6") (pin "1") (pinfunction "1_1") (pintype "passive"))
      (node (ref "D3") (pin "C") (pinfunction "C_C") (pintype "passive"))
      (node (ref "L2") (pin "2") (pinfunction "2_2") (pintype "passive"))
      (node (ref "R10") (pin "2") (pinfunction "2_2") (pintype "passive"))
      (node (ref "U11") (pin "13") (pinfunction "PVDDR_13") (pintype "bidirectional"))
      (node (ref "U11") (pin "4") (pinfunction "PVDDL_4") (pintype "bidirectional"))
      (node (ref "U11") (pin "6") (pinfunction "VDD_6") (pintype "bidirectional"))
      (node (ref "U11") (pin "9") (pinfunction "MODE_9") (pintype "input"))
      (node (ref "U3") (pin "15") (pinfunction "VCC_15") (pintype "bidirectional"))
      (node (ref "U4") (pin "4") (pinfunction "CE_4") (pintype "power_in"))
      (node (ref "U5") (pin "1") (pinfunction "VIN_1") (pintype "power_in"))
      (node (ref "U5") (pin "3") (pinfunction "CE_3") (pintype "power_in"))
      (node (ref "U9") (pin "19") (pinfunction "VDD_19") (pintype "bidirectional"))
      (node (ref "U9") (pin "20") (pinfunction "MDAT_20") (pintype "bidirectional"))
      (node (ref "U9") (pin "23") (pinfunction "EMPH_23") (pintype "bidirectional"))
      (node (ref "U9") (pin "24") (pinfunction "BLSM_24") (pintype "bidirectional"))
      (node (ref "U9") (pin "28") (pinfunction "MODE_28") (pintype "bidirectional"))
      (node (ref "U9") (pin "5") (pinfunction "CS/CLK0_5") (pintype "bidirectional"))
      (node (ref "U9") (pin "7") (pinfunction "VIO_7") (pintype "bidirectional"))
      (node (ref "U9") (pin "9") (pinfunction "RXP/FMT0_9") (pintype "bidirectional"))
    )
    (net (code "3") (name "12V") (class "Default")
      (node (ref "C2") (pin "1") (pinfunction "1_1") (pintype "passive"))
      (node (ref "Q3") (pin "2") (pinfunction "S_2") (pintype "bidirectional"))
      (node (ref "R28") (pin "1") (pinfunction "1_1") (pintype "passive"))
      (node (ref "R5") (pin "2") (pinfunction "2_2") (pintype "passive"))
      (node (ref "U4") (pin "5") (pinfunction "VOUT_5") (pintype "power_in"))
    )
    (net (code "4") (name "AGND") (class "Default")
      (node (ref "C50") (pin "2") (pinfunction "2_2") (pintype "passive"))
      (node (ref "C51") (pin "2") (pinfunction "2_2") (pintype "passive"))
      (node (ref "C53") (pin "1") (pinfunction "1_1") (pintype "passive"))
      (node (ref "C55") (pin "2") (pinfunction "2_2") (pintype "passive"))
      (node (ref "C56") (pin "2") (pinfunction "2_2") (pintype "passive"))
      (node (ref "C57") (pin "2") (pinfunction "2_2") (pintype "passive"))
      (node (ref "C58") (pin "2") (pinfunction "2_2") (pintype "passive"))
      (node (ref "J2") (pin "2") (pinfunction "2_2") (pintype "bidirectional"))
      (node (ref "J2") (pin "5") (pinfunction "5_5") (pintype "bidirectional"))
      (node (ref "SH1") (pin "2") (pinfunction "P$2_2") (pintype "bidirectional"))
      (node (ref "U10") (pin "10") (pinfunction "VCOM/DEMP_10") (pintype "input"))
      (node (ref "U10") (pin "3") (pinfunction "CPGND_3") (pintype "bidirectional"))
      (node (ref "U10") (pin "9") (pinfunction "AGND_9") (pintype "bidirectional"))
    )
    (net (code "5") (name "BT_MFB") (class "Default")
      (node (ref "U7") (pin "1") (pinfunction "IC4/CTED4/PMD5/RE5_1") (pintype "bidirectional"))
      (node (ref "U8") (pin "26") (pinfunction "PWR_(MFB)_26") (pintype "bidirectional"))
    )
    (net (code "6") (name "BT_MIC_L") (class "Default")
      (node (ref "C32") (pin "1") (pinfunction "1_1") (pintype "passive"))
      (node (ref "C33") (pin "1") (pinfunction "1_1") (pintype "passive"))
      (node (ref "C40") (pin "1") (pinfunction "1_1") (pintype "passive"))
      (node (ref "J4") (pin "2") (pinfunction "TIP_2") (pintype "passive"))
      (node (ref "R27") (pin "1") (pinfunction "1_1") (pintype "passive"))
    )
    (net (code "7") (name "BT_MODE") (class "Default")
      (node (ref "U7") (pin "61") (pinfunction "PMD1/RE1_61") (pintype "bidirectional"))
      (node (ref "U8") (pin "31") (pinfunction "P3_4/UART_RTS_31") (pintype "bidirectional"))
    )
    (net (code "8") (name "BT_RST") (class "Default")
      (node (ref "U7") (pin "58") (pinfunction "U5CTS/OC6/RF0_58") (pintype "bidirectional"))
      (node (ref "U8") (pin "43") (pinfunction "RST_N_43") (pintype "bidirectional"))
    )
    (net (code "9") (name "BT_URX") (class "Default")
      (node (ref "U7") (pin "4") (pinfunction "C1IND/RP21/ICM1/OCM1A/PMA5/RG6_4") (pintype "bidirectional"))
      (node (ref "U8") (pin "30") (pinfunction "P8_5/UART_TXD_30") (pintype "bidirectional"))
    )
    (net (code "10") (name "BT_UTX") (class "Default")
      (node (ref "U7") (pin "5") (pinfunction "C1INC/RP26/OCM1B/PMA4/RG7_5") (pintype "bidirectional"))
      (node (ref "U8") (pin "29") (pinfunction "P8_6/UART_RXD_29") (pintype "bidirectional"))
    )
    (net (code "11") (name "DAC_3V3") (class "Default")
      (node (ref "C50") (pin "1") (pinfunction "1_1") (pintype "passive"))
      (node (ref "C51") (pin "1") (pinfunction "1_1") (pintype "passive"))
      (node (ref "C57") (pin "1") (pinfunction "1_1") (pintype "passive"))
      (node (ref "C58") (pin "1") (pinfunction "1_1") (pintype "passive"))
      (node (ref "C61") (pin "1") (pinfunction "1_1") (pintype "passive"))
      (node (ref "C62") (pin "1") (pinfunction "1_1") (pintype "passive"))
      (node (ref "FB4") (pin "2") (pinfunction "2_2") (pintype "bidirectional"))
      (node (ref "U10") (pin "1") (pinfunction "CPVDD_1") (pintype "power_in"))
      (node (ref "U10") (pin "18") (pinfunction "MODE2/MS_18") (pintype "bidirectional"))
      (node (ref "U10") (pin "25") (pinfunction "XSMT_25") (pintype "input"))
      (node (ref "U10") (pin "28") (pinfunction "DVDD_28") (pintype "power_in"))
      (node (ref "U10") (pin "8") (pinfunction "AVDD_8") (pintype "power_in"))
    )
    (net (code "12") (name "DAC_OUT_L") (class "Default")
      (node (ref "FB3") (pin "1") (pinfunction "1_1") (pintype "bidirectional"))
      (node (ref "R32") (pin "1") (pinfunction "1_1") (pintype "passive"))
      (node (ref "U10") (pin "6") (pinfunction "OUTL_6") (pintype "output"))
    )
    (net (code "13") (name "EE_CS") (class "Default")
      (node (ref "R14") (pin "1") (pinfunction "1_1") (pintype "passive"))
      (node (ref "U6") (pin "1") (pinfunction "CE_1") (pintype "bidirectional"))
      (node (ref "U7") (pin "42") (pinfunction "CLC4OUT/RP2/U6RTS/U6BCLK/ICM5/RD8_42") (pintype "bidirectional"))
    )
    (net (code "14") (name "EE_SCK") (class "Default")
      (node (ref "U6") (pin "6") (pinfunction "SCK_6") (pintype "bidirectional"))
      (node (ref "U7") (pin "33") (pinfunction "RP16/RF3_33") (pintype "bidirectional"))
    )
    (net (code "15") (name "EE_SI") (class "Default")
      (node (ref "U6") (pin "5") (pinfunction "SI_5") (pintype "bidirectional"))
      (node (ref "U7") (pin "34") (pinfunction "RP30/RF2_34") (pintype "bidirectional"))
    )
    (net (code "16") (name "EE_SO") (class "Default")
      (node (ref "U6") (pin "2") (pinfunction "SO_2") (pintype "bidirectional"))
      (node (ref "U7") (pin "43") (pinfunction "RP4/PMACK2/RD9_43") (pintype "bidirectional"))
    )
    (net (code "17") (name "GND") (class "Default")
      (node (ref "C1") (pin "2") (pinfunction "2_2") (pintype "passive"))
      (node (ref "C10") (pin "2") (pinfunction "2_2") (pintype "passive"))
      (node (ref "C11") (pin "2") (pinfunction "2_2") (pintype "passive"))
      (node (ref "C12") (pin "2") (pinfunction "2_2") (pintype "passive"))
      (node (ref "C13") (pin "2") (pinfunction "2_2") (pintype "passive"))
      (node (ref "C14") (pin "1") (pinfunction "1_1") (pintype "passive"))
      (node (ref "C15") (pin "1") (pinfunction "1_1") (pintype "passive"))
      (node (ref "C16") (pin "1") (pinfunction "1_1") (pintype "passive"))
      (node (ref "C17") (pin "1") (pinfunction "1_1") (pintype "passive"))
      (node (ref "C18") (pin "2") (pinfunction "2_2") (pintype "passive"))
      (node (ref "C19") (pin "2") (pinfunction "2_2") (pintype "passive"))
      (node (ref "C2") (pin "2") (pinfunction "2_2") (pintype "passive"))
      (node (ref "C20") (pin "2") (pinfunction "2_2") (pintype "passive"))
      (node (ref "C21") (pin "1") (pinfunction "1_1") (pintype "passive"))
      (node (ref "C22") (pin "2") (pinfunction "2_2") (pintype "passive"))
      (node (ref "C23") (pin "2") (pinfunction "2_2") (pintype "passive"))
      (node (ref "C24") (pin "2") (pinfunction "2_2") (pintype "passive"))
      (node (ref "C25") (pin "2") (pinfunction "2_2") (pintype "passive"))
      (node (ref "C26") (pin "2") (pinfunction "2_2") (pintype "passive"))
      (node (ref "C27") (pin "2") (pinfunction "2_2") (pintype "passive"))
      (node (ref "C28") (pin "2") (pinfunction "2_2") (pintype "passive"))
      (node (ref "C29") (pin "2") (pinfunction "2_2") (pintype "passive"))
      (node (ref "C3") (pin "2") (pinfunction "2_2") (pintype "passive"))
      (node (ref "C30") (pin "2") (pinfunction "2_2") (pintype "passive"))
      (node (ref "C31") (pin "1") (pinfunction "1_1") (pintype "passive"))
      (node (ref "C32") (pin "2") (pinfunction "2_2") (pintype "passive"))
      (node (ref "C34") (pin "2") (pinfunction "2_2") (pintype "passive"))
      (node (ref "C35") (pin "2") (pinfunction "2_2") (pintype "passive"))
      (node (ref "C36") (pin "2") (pinfunction "2_2") (pintype "passive"))
      (node (ref "C37") (pin "2") (pinfunction "2_2") (pintype "passive"))
      (node (ref "C38") (pin "2") (pinfunction "2_2") (pintype "passive"))
      (node (ref "C39") (pin "2") (pinfunction "2_2") (pintype "passive"))
      (node (ref "C4") (pin "2") (pinfunction "2_2") (pintype "passive"))
      (node (ref "C41") (pin "2") (pinfunction "2_2") (pintype "passive"))
      (node (ref "C42") (pin "2") (pinfunction "2_2") (pintype "passive"))
      (node (ref "C43") (pin "2") (pinfunction "2_2") (pintype "passive"))
      (node (ref "C44") (pin "2") (pinfunction "2_2") (pintype "passive"))
      (node (ref "C45") (pin "2") (pinfunction "2_2") (pintype "passive"))
      (node (ref "C46") (pin "2") (pinfunction "2_2") (pintype "passive"))
      (node (ref "C47") (pin "2") (pinfunction "2_2") (pintype "passive"))
      (node (ref "C48") (pin "2") (pinfunction "2_2") (pintype "passive"))
      (node (ref "C5") (pin "2") (pinfunction "2_2") (pintype "passive"))
      (node (ref "C59") (pin "2") (pinfunction "2_2") (pintype "passive"))
      (node (ref "C6") (pin "2") (pinfunction "2_2") (pintype "passive"))
      (node (ref "C60") (pin "2") (pinfunction "2_2") (pintype "passive"))
      (node (ref "C61") (pin "2") (pinfunction "2_2") (pintype "passive"))
      (node (ref "C62") (pin "2") (pinfunction "2_2") (pintype "passive"))
      (node (ref "C8") (pin "2") (pinfunction "2_2") (pintype "passive"))
      (node (ref "C9") (pin "2") (pinfunction "2_2") (pintype "passive"))
      (node (ref "J3") (pin "4") (pinfunction "4_4") (pintype "bidirectional"))
      (node (ref "J4") (pin "1") (pinfunction "SLEEVE_1") (pintype "passive"))
      (node (ref "J6") (pin "5") (pinfunction "GND_5") (pintype "power_in"))
      (node (ref "J6") (pin "MNT1") (pinfunction "SHIELD_MNT1") (pintype "bidirectional"))
      (node (ref "J6") (pin "MNT2") (pinfunction "SHIELD_MNT2") (pintype "bidirectional"))
      (node (ref "J6") (pin "MNT3") (pinfunction "SHIELD_MNT3") (pintype "bidirectional"))
      (node (ref "J6") (pin "MNT4") (pinfunction "SHIELD_MNT4") (pintype "bidirectional"))
      (node (ref "J7") (pin "3") (pinfunction "3_3") (pintype "bidirectional"))
      (node (ref "J7") (pin "4") (pinfunction "GND_4") (pintype "bidirectional"))
      (node (ref "J7") (pin "5") (pinfunction "GND_5") (pintype "bidirectional"))
      (node (ref "J7") (pin "6") (pinfunction "GND_6") (pintype "bidirectional"))
      (node (ref "J7") (pin "7") (pinfunction "GND_7") (pintype "bidirectional"))
      (node (ref "J8") (pin "3") (pinfunction "3_3") (pintype "bidirectional"))
      (node (ref "L1") (pin "3") (pinfunction "3_3") (pintype "passive"))
      (node (ref "PWR") (pin "-") (pinfunction "C_-") (pintype "passive"))
      (node (ref "Q1") (pin "2") (pinfunction "S_2") (pintype "bidirectional"))
      (node (ref "Q2") (pin "2") (pinfunction "S_2") (pintype "bidirectional"))
      (node (ref "R11") (pin "1") (pinfunction "1_1") (pintype "passive"))
      (node (ref "R2") (pin "2") (pinfunction "2_2") (pintype "passive"))
      (node (ref "R30") (pin "2") (pinfunction "2_2") (pintype "passive"))
      (node (ref "R4") (pin "1") (pinfunction "1_1") (pintype "passive"))
      (node (ref "SH1") (pin "1") (pinfunction "P$1_1") (pintype "bidirectional"))
      (node (ref "U1") (pin "4") (pinfunction "GND_4") (pintype "bidirectional"))
      (node (ref "U10") (pin "16") (pinfunction "ADR2/GPIO2/DOUT_16") (pintype "bidirectional"))
      (node (ref "U10") (pin "17") (pinfunction "MODE1_17") (pintype "bidirectional"))
      (node (ref "U10") (pin "24") (pinfunction "ADR1/MISO/FMT_24") (pintype "input"))
      (node (ref "U10") (pin "27") (pinfunction "DGND_27") (pintype "bidirectional"))
      (node (ref "U11") (pin "10") (pinfunction "INR_10") (pintype "input"))
      (node (ref "U11") (pin "11") (pinfunction "GND_11") (pintype "bidirectional"))
      (node (ref "U11") (pin "15") (pinfunction "PGNDR_15") (pintype "bidirectional"))
      (node (ref "U11") (pin "2") (pinfunction "PGNDL_2") (pintype "bidirectional"))
      (node (ref "U2") (pin "12") (pinfunction "GND3_12") (pintype "passive"))
      (node (ref "U2") (pin "13") (pinfunction "GND4_13") (pintype "passive"))
      (node (ref "U2") (pin "3") (pinfunction "VTR_3") (pintype "input"))
      (node (ref "U2") (pin "4") (pinfunction "GND1_4") (pintype "passive"))
      (node (ref "U2") (pin "5") (pinfunction "GND2_5") (pintype "passive"))
      (node (ref "U2") (pin "7") (pinfunction "SI_7") (pintype "bidirectional"))
      (node (ref "U3") (pin "16") (pinfunction "GND_16") (pintype "bidirectional"))
      (node (ref "U3") (pin "6") (pinfunction "GND_6") (pintype "bidirectional"))
      (node (ref "U4") (pin "2") (pinfunction "GND_2") (pintype "power_in"))
      (node (ref "U5") (pin "2") (pinfunction "GND_2") (pintype "power_in"))
      (node (ref "U6") (pin "4") (pinfunction "VSS_4") (pintype "power_in"))
      (node (ref "U7") (pin "20") (pinfunction "AVSS_20") (pintype "power_in"))
      (node (ref "U7") (pin "25") (pinfunction "VSS_25") (pintype "power_in"))
      (node (ref "U7") (pin "41") (pinfunction "VSS_41") (pintype "power_in"))
      (node (ref "U7") (pin "9") (pinfunction "VSS_9") (pintype "power_in"))
      (node (ref "U8") (pin "16") (pinfunction "GND_1_16") (pintype "bidirectional"))
      (node (ref "U8") (pin "50") (pinfunction "GND_2_50") (pintype "bidirectional"))
      (node (ref "U8") (pin "EP1") (pinfunction "EP1_EP1") (pintype "bidirectional"))
      (node (ref "U8") (pin "EP2") (pinfunction "EP2_EP2") (pintype "bidirectional"))
      (node (ref "U9") (pin "1") (pinfunction "CSS_1") (pintype "bidirectional"))
      (node (ref "U9") (pin "10") (pinfunction "FMT1_10") (pintype "bidirectional"))
      (node (ref "U9") (pin "14") (pinfunction "M/S_14") (pintype "bidirectional"))
      (node (ref "U9") (pin "16") (pinfunction "DGND2_16") (pintype "bidirectional"))
      (node (ref "U9") (pin "2") (pinfunction "CDOUT/COPY_2") (pintype "bidirectional"))
      (node (ref "U9") (pin "21") (pinfunction "MONO_21") (pintype "bidirectional"))
      (node (ref "U9") (pin "22") (pinfunction "INT/AUDIO_22") (pintype "bidirectional"))
      (node (ref "U9") (pin "26") (pinfunction "V_26") (pintype "bidirectional"))
      (node (ref "U9") (pin "27") (pinfunction "U_27") (pintype "bidirectional"))
      (node (ref "U9") (pin "3") (pinfunction "CCLK/L_3") (pintype "bidirectional"))
      (node (ref "U9") (pin "4") (pinfunction "CDIN/CLK1_4") (pintype "bidirectional"))
      (node (ref "U9") (pin "8") (pinfunction "DGND1_8") (pintype "bidirectional"))
    )
    (net (code "18") (name "GND_FLT") (class "Default")
      (node (ref "D2") (pin "A") (pinfunction "A_A") (pintype "passive"))
      (node (ref "J1") (pin "1") (pinfunction "1_1") (pintype "passive"))
      (node (ref "J5") (pin "1") (pinfunction "GND_1") (pintype "bidirectional"))
      (node (ref "J5") (pin "2") (pinfunction "GND_2") (pintype "bidirectional"))
      (node (ref "J5") (pin "3") (pinfunction "GND_3") (pintype "bidirectional"))
      (node (ref "J5") (pin "4") (pinfunction "GND_4") (pintype "bidirectional"))
      (node (ref "L1") (pin "2") (pinfunction "2_2") (pintype "passive"))
    )
    (net (code "19") (name "I2S_BCK") (class "Default")
      (node (ref "U10") (pin "21") (pinfunction "BCK_21") (pintype "input"))
      (node (ref "U8") (pin "3") (pinfunction "SCLK1_3") (pintype "bidirectional"))
      (node (ref "U9") (pin "11") (pinfunction "SCLK_11") (pintype "bidirectional"))
    )
    (net (code "20") (name "I2S_DOUT") (class "Default")
      (node (ref "U10") (pin "22") (pinfunction "DIN_22") (pintype "input"))
      (node (ref "U8") (pin "4") (pinfunction "DT1_4") (pintype "bidirectional"))
      (node (ref "U9") (pin "13") (pinfunction "SDATA_13") (pintype "bidirectional"))
    )
    (net (code "21") (name "I2S_LRCK") (class "Default")
      (node (ref "U10") (pin "23") (pinfunction "LRCK_23") (pintype "input"))
      (node (ref "U8") (pin "2") (pinfunction "RFS1_2") (pintype "bidirectional"))
      (node (ref "U9") (pin "12") (pinfunction "SYNC_12") (pintype "bidirectional"))
    )
    (net (code "22") (name "I2S_MCLK") (class "Default")
      (node (ref "U10") (pin "20") (pinfunction "SCK_20") (pintype "input"))
      (node (ref "U8") (pin "5") (pinfunction "MCLK1_5") (pintype "bidirectional"))
      (node (ref "U9") (pin "6") (pinfunction "MCLK_6") (pintype "bidirectional"))
    )
    (net (code "23") (name "IBUS") (class "Default")
      (node (ref "J1") (pin "3") (pinfunction "3_3") (pintype "passive"))
      (node (ref "R21") (pin "1") (pinfunction "1_1") (pintype "passive"))
      (node (ref "R22") (pin "1") (pinfunction "1_1") (pintype "passive"))
      (node (ref "R34") (pin "1") (pinfunction "1_1") (pintype "passive"))
    )
    (net (code "24") (name "IBUS_5V") (class "Default")
      (node (ref "C21") (pin "2") (pinfunction "2_2") (pintype "passive"))
      (node (ref "R8") (pin "2") (pinfunction "2_2") (pintype "passive"))
      (node (ref "U2") (pin "16") (pinfunction "VCC_16") (pintype "passive"))
    )
    (net (code "25") (name "IBUS_EN") (class "Default")
      (node (ref "U2") (pin "2") (pinfunction "EN_2") (pintype "input"))
      (node (ref "U7") (pin "59") (pinfunction "RF1_59") (pintype "bidirectional"))
    )
    (net (code "26") (name "IBUS_URX") (class "Default")
      (node (ref "U2") (pin "10") (pinfunction "RXD_10") (pintype "output"))
      (node (ref "U7") (pin "45") (pinfunction "RP12/PMA14/PMCS1/RD11_45") (pintype "bidirectional"))
    )
    (net (code "27") (name "IBUS_USTA") (class "Default")
      (node (ref "U2") (pin "9") (pinfunction "SEN/STA_9") (pintype "bidirectional"))
      (node (ref "U7") (pin "46") (pinfunction "CLC3OUT/RP11/U6CTS/ICM6/RD0_46") (pintype "bidirectional"))
    )
    (net (code "28") (name "IBUS_UTX") (class "Default")
      (node (ref "U2") (pin "11") (pinfunction "TXD_11") (pintype "input"))
      (node (ref "U7") (pin "44") (pinfunction "RP3/PMA15/PMCS2/RD10_44") (pintype "bidirectional"))
    )
    (net (code "29") (name "MCU_MCLR") (class "Default")
      (node (ref "J8") (pin "1") (pinfunction "1_1") (pintype "bidirectional"))
      (node (ref "R18") (pin "2") (pinfunction "2_2") (pintype "passive"))
      (node (ref "U7") (pin "7") (pinfunction "MCLR_7") (pintype "bidirectional"))
    )
    (net (code "30") (name "MCU_PGC") (class "Default")
      (node (ref "J8") (pin "5") (pinfunction "5_5") (pintype "bidirectional"))
      (node (ref "U7") (pin "15") (pinfunction "PGEC1_15") (pintype "bidirectional"))
    )
    (net (code "31") (name "MCU_PGD") (class "Default")
      (node (ref "J8") (pin "4") (pinfunction "4_4") (pintype "bidirectional"))
      (node (ref "U7") (pin "16") (pinfunction "PGED1_16") (pintype "bidirectional"))
    )
    (net (code "32") (name "MCU_RECOVERY") (class "Default")
      (node (ref "J7") (pin "2") (pinfunction "2_2") (pintype "bidirectional"))
      (node (ref "U7") (pin "53") (pinfunction "RP20/PMRD/PMWR/RD5_53") (pintype "bidirectional"))
    )
    (net (code "33") (name "MCU_SCK3") (class "Default")
      (node (ref "R16") (pin "1") (pinfunction "1_1") (pintype "passive"))
      (node (ref "U10") (pin "12") (pinfunction "SCL/MC/ATT1_12") (pintype "bidirectional"))
      (node (ref "U7") (pin "2") (pinfunction "SCL3/IC5/PMD6/RE6_2") (pintype "bidirectional"))
    )
    (net (code "34") (name "MCU_SDA3") (class "Default")
      (node (ref "R15") (pin "1") (pinfunction "1_1") (pintype "passive"))
      (node (ref "U10") (pin "11") (pinfunction "SDA/MOSI/ATT2_11") (pintype "bidirectional"))
      (node (ref "U7") (pin "3") (pinfunction "SDA3/IC6/PMD7/RE7_3") (pintype "bidirectional"))
    )
    (net (code "35") (name "MCU_TEL_MUTE") (class "Default")
      (node (ref "R1") (pin "1") (pinfunction "1_1") (pintype "passive"))
      (node (ref "R2") (pin "1") (pinfunction "1_1") (pintype "passive"))
      (node (ref "U7") (pin "31") (pinfunction "RP10/SDA2/PMA9/RF4_31") (pintype "bidirectional"))
    )
    (net (code "36") (name "MCU_TEL_ON") (class "Default")
      (node (ref "R3") (pin "1") (pinfunction "1_1") (pintype "passive"))
      (node (ref "R4") (pin "2") (pinfunction "2_2") (pintype "passive"))
      (node (ref "U7") (pin "32") (pinfunction "RP17/SCL2/PMA8/RF5_32") (pintype "bidirectional"))
    )
    (net (code "37") (name "MCU_VER") (class "Default")
      (node (ref "R19") (pin "1") (pinfunction "1_1") (pintype "passive"))
      (node (ref "U7") (pin "6") (pinfunction "C2IND/RP19/ICM2/OCM2A/PMA3/RG8_6") (pintype "bidirectional"))
    )
    (net (code "38") (name "MICN1") (class "Default")
      (node (ref "C31") (pin "2") (pinfunction "2_2") (pintype "passive"))
      (node (ref "U8") (pin "13") (pinfunction "MICN1_13") (pintype "bidirectional"))
    )
    (net (code "39") (name "MICP1") (class "Default")
      (node (ref "C33") (pin "2") (pinfunction "2_2") (pintype "passive"))
      (node (ref "U8") (pin "14") (pinfunction "MICP1_14") (pintype "bidirectional"))
    )
    (net (code "40") (name "MIC_BIAS") (class "Default")
      (node (ref "C34") (pin "1") (pinfunction "1_1") (pintype "passive"))
      (node (ref "R26") (pin "2") (pinfunction "2_2") (pintype "passive"))
      (node (ref "U8") (pin "15") (pinfunction "MICBIAS_15") (pintype "bidirectional"))
    )
    (net (code "41") (name "Net-(C7-Pad1)") (class "Default")
      (node (ref "C7") (pin "1") (pinfunction "1_1") (pintype "passive"))
      (node (ref "R9") (pin "2") (pinfunction "2_2") (pintype "passive"))
    )
    (net (code "42") (name "Net-(C20-Pad1)") (class "Default")
      (node (ref "C20") (pin "1") (pinfunction "1_1") (pintype "passive"))
      (node (ref "R17") (pin "2") (pinfunction "2_2") (pintype "passive"))
      (node (ref "R18") (pin "1") (pinfunction "1_1") (pintype "passive"))
    )
    (net (code "43") (name "Net-(C35-Pad1)") (class "Default")
      (node (ref "C35") (pin "1") (pinfunction "1_1") (pintype "passive"))
      (node (ref "R26") (pin "1") (pinfunction "1_1") (pintype "passive"))
      (node (ref "R27") (pin "2") (pinfunction "2_2") (pintype "passive"))
    )
    (net (code "44") (name "Net-(C49-Pad1)") (class "Default")
      (node (ref "C49") (pin "1") (pinfunction "1_1") (pintype "passive"))
      (node (ref "FB3") (pin "2") (pinfunction "2_2") (pintype "bidirectional"))
    )
    (net (code "45") (name "Net-(C49-Pad2)") (class "Default")
      (node (ref "C49") (pin "2") (pinfunction "2_2") (pintype "passive"))
      (node (ref "R29") (pin "1") (pinfunction "1_1") (pintype "passive"))
    )
    (net (code "46") (name "Net-(C52-Pad2)") (class "Default")
      (node (ref "C52") (pin "2") (pinfunction "2_2") (pintype "passive"))
      (node (ref "R31") (pin "1") (pinfunction "1_1") (pintype "passive"))
    )
    (net (code "47") (name "Net-(F1-OUT)") (class "Default")
      (node (ref "D1") (pin "C") (pinfunction "C_C") (pintype "passive"))
      (node (ref "D2") (pin "C") (pinfunction "C_C") (pintype "passive"))
      (node (ref "F1") (pin "IN") (pinfunction "OUT_IN") (pintype "bidirectional"))
    )
    (net (code "48") (name "Net-(J7-Pad1)") (class "Default")
      (node (ref "J7") (pin "1") (pinfunction "1_1") (pintype "bidirectional"))
      (node (ref "R20") (pin "1") (pinfunction "1_1") (pintype "passive"))
    )
    (net (code "49") (name "Net-(PWR-A)") (class "Default")
      (node (ref "PWR") (pin "+") (pinfunction "A_+") (pintype "passive"))
      (node (ref "R23") (pin "1") (pinfunction "1_1") (pintype "passive"))
    )
    (net (code "50") (name "Net-(Q1-G)") (class "Default")
      (node (ref "Q1") (pin "1") (pinfunction "G_1") (pintype "bidirectional"))
      (node (ref "R1") (pin "2") (pinfunction "2_2") (pintype "passive"))
    )
    (net (code "51") (name "Net-(Q2-D)") (class "Default")
      (node (ref "Q2") (pin "3") (pinfunction "D_3") (pintype "bidirectional"))
      (node (ref "R5") (pin "1") (pinfunction "1_1") (pintype "passive"))
      (node (ref "R6") (pin "1") (pinfunction "1_1") (pintype "passive"))
    )
    (net (code "52") (name "Net-(Q2-G)") (class "Default")
      (node (ref "Q2") (pin "1") (pinfunction "G_1") (pintype "bidirectional"))
      (node (ref "R3") (pin "2") (pinfunction "2_2") (pintype "passive"))
    )
    (net (code "53") (name "Net-(Q3-D)") (class "Default")
      (node (ref "Q3") (pin "3") (pinfunction "D_3") (pintype "bidirectional"))
      (node (ref "R7") (pin "1") (pinfunction "1_1") (pintype "passive"))
    )
    (net (code "54") (name "Net-(Q3-G)") (class "Default")
      (node (ref "Q3") (pin "1") (pinfunction "G_1") (pintype "bidirectional"))
      (node (ref "R6") (pin "2") (pinfunction "2_2") (pintype "passive"))
    )
    (net (code "55") (name "Net-(R10-Pad1)") (class "Default")
      (node (ref "R10") (pin "1") (pinfunction "1_1") (pintype "passive"))
      (node (ref "R11") (pin "2") (pinfunction "2_2") (pintype "passive"))
      (node (ref "R12") (pin "1") (pinfunction "1_1") (pintype "passive"))
    )
    (net (code "56") (name "Net-(R34-Pad2)") (class "Default")
      (node (ref "R34") (pin "2") (pinfunction "2_2") (pintype "passive"))
      (node (ref "SW1") (pin "1") (pinfunction "1_1") (pintype "bidirectional"))
    )
    (net (code "57") (name "Net-(RX-C)") (class "Default")
      (node (ref "R24") (pin "1") (pinfunction "1_1") (pintype "passive"))
      (node (ref "RX") (pin "-") (pinfunction "C_-") (pintype "passive"))
    )
    (net (code "58") (name "Net-(TX-C)") (class "Default")
      (node (ref "R25") (pin "1") (pinfunction "1_1") (pintype "passive"))
      (node (ref "TX") (pin "-") (pinfunction "C_-") (pintype "passive"))
    )
    (net (code "59") (name "Net-(U1-BS)") (class "Default")
      (node (ref "R9") (pin "1") (pinfunction "1_1") (pintype "passive"))
      (node (ref "U1") (pin "5") (pinfunction "BS_5") (pintype "bidirectional"))
    )
    (net (code "60") (name "Net-(U1-EN)") (class "Default")
      (node (ref "R8") (pin "1") (pinfunction "1_1") (pintype "passive"))
      (node (ref "U1") (pin "6") (pinfunction "EN_6") (pintype "bidirectional"))
    )
    (net (code "61") (name "Net-(U1-FB)") (class "Default")
      (node (ref "R12") (pin "2") (pinfunction "2_2") (pintype "passive"))
      (node (ref "U1") (pin "8") (pinfunction "FB_8") (pintype "bidirectional"))
    )
    (net (code "62") (name "Net-(U1-PG)") (class "Default")
      (node (ref "R13") (pin "1") (pinfunction "1_1") (pintype "passive"))
      (node (ref "U1") (pin "1") (pinfunction "PG_1") (pintype "bidirectional"))
    )
    (net (code "63") (name "Net-(U1-SW)") (class "Default")
      (node (ref "C7") (pin "2") (pinfunction "2_2") (pintype "passive"))
      (node (ref "L2") (pin "1") (pinfunction "1_1") (pintype "passive"))
      (node (ref "U1") (pin "3") (pinfunction "SW_3") (pintype "bidirectional"))
    )
    (net (code "64") (name "Net-(U1-VCC)") (class "Default")
      (node (ref "C8") (pin "1") (pinfunction "1_1") (pintype "passive"))
      (node (ref "R13") (pin "2") (pinfunction "2_2") (pintype "passive"))
      (node (ref "U1") (pin "7") (pinfunction "VCC_7") (pintype "bidirectional"))
    )
    (net (code "65") (name "Net-(U2-IBUS)") (class "Default")
      (node (ref "C23") (pin "1") (pinfunction "1_1") (pintype "passive"))
      (node (ref "R21") (pin "2") (pinfunction "2_2") (pintype "passive"))
      (node (ref "R22") (pin "2") (pinfunction "2_2") (pintype "passive"))
      (node (ref "U2") (pin "6") (pinfunction "IBUS_6") (pintype "bidirectional"))
    )
    (net (code "66") (name "Net-(U3-CBUS1)") (class "Default")
      (node (ref "R24") (pin "2") (pinfunction "2_2") (pintype "passive"))
      (node (ref "U3") (pin "17") (pinfunction "CBUS1_17") (pintype "bidirectional"))
    )
    (net (code "67") (name "Net-(U3-CBUS2)") (class "Default")
      (node (ref "R25") (pin "2") (pinfunction "2_2") (pintype "passive"))
      (node (ref "U3") (pin "10") (pinfunction "CBUS2_10") (pintype "bidirectional"))
    )
    (net (code "68") (name "Net-(U7-PMD0{slash}RE0)") (class "Default")
      (node (ref "R23") (pin "2") (pinfunction "2_2") (pintype "passive"))
      (node (ref "U7") (pin "60") (pinfunction "PMD0/RE0_60") (pintype "bidirectional"))
    )
    (net (code "69") (name "Net-(U7-VCAP)") (class "Default")
      (node (ref "C18") (pin "1") (pinfunction "1_1") (pintype "passive"))
      (node (ref "C19") (pin "1") (pinfunction "1_1") (pintype "passive"))
      (node (ref "U7") (pin "56") (pinfunction "VCAP_56") (pintype "passive"))
    )
    (net (code "70") (name "Net-(U8-SYS_PWR)") (class "Default")
      (node (ref "C29") (pin "1") (pinfunction "1_1") (pintype "passive"))
      (node (ref "U8") (pin "24") (pinfunction "SYS_PWR_24") (pintype "bidirectional"))
    )
    (net (code "71") (name "Net-(U8-VDD_IO)") (class "Default")
      (node (ref "C30") (pin "1") (pinfunction "1_1") (pintype "passive"))
      (node (ref "U8") (pin "25") (pinfunction "VDD_IO_25") (pintype "bidirectional"))
    )
    (net (code "72") (name "Net-(U9-TX+)") (class "Default")
      (node (ref "C52") (pin "1") (pinfunction "1_1") (pintype "passive"))
      (node (ref "U9") (pin "18") (pinfunction "TX+_18") (pintype "bidirectional"))
    )
    (net (code "73") (name "Net-(U10-CAPM)") (class "Default")
      (node (ref "C54") (pin "2") (pinfunction "2_2") (pintype "passive"))
      (node (ref "U10") (pin "4") (pinfunction "CAPM_4") (pintype "output"))
    )
    (net (code "74") (name "Net-(U10-CAPP)") (class "Default")
      (node (ref "C54") (pin "1") (pinfunction "1_1") (pintype "passive"))
      (node (ref "U10") (pin "2") (pinfunction "CAPP_2") (pintype "output"))
    )
    (net (code "75") (name "Net-(U10-LDOO)") (class "Default")
      (node (ref "C59") (pin "1") (pinfunction "1_1") (pintype "passive"))
      (node (ref "C60") (pin "1") (pinfunction "1_1") (pintype "passive"))
      (node (ref "U10") (pin "26") (pinfunction "LDOO_26") (pintype "power_in"))
    )
    (net (code "76") (name "Net-(U10-OUTR)") (class "Default")
      (node (ref "R33") (pin "1") (pinfunction "1_1") (pintype "passive"))
      (node (ref "U10") (pin "7") (pinfunction "OUTR_7") (pintype "output"))
    )
    (net (code "77") (name "Net-(U10-VNEG)") (class "Default")
      (node (ref "C53") (pin "2") (pinfunction "2_2") (pintype "passive"))
      (node (ref "U10") (pin "5") (pinfunction "VNEG_5") (pintype "output"))
    )
    (net (code "78") (name "Net-(U11-INL)") (class "Default")
      (node (ref "R29") (pin "2") (pinfunction "2_2") (pintype "passive"))
      (node (ref "U11") (pin "7") (pinfunction "INL_7") (pintype "input"))
    )
    (net (code "79") (name "Net-(U11-OUT_L+)") (class "Default")
      (node (ref "FB2") (pin "1") (pinfunction "1_1") (pintype "bidirectional"))
      (node (ref "U11") (pin "1") (pinfunction "OUT_L+_1") (pintype "output"))
    )
    (net (code "80") (name "Net-(U11-OUT_L-)") (class "Default")
      (node (ref "FB1") (pin "1") (pinfunction "1_1") (pintype "bidirectional"))
      (node (ref "U11") (pin "3") (pinfunction "OUT_L-_3") (pintype "output"))
    )
    (net (code "81") (name "Net-(U11-VREF)") (class "Default")
      (node (ref "C48") (pin "1") (pinfunction "1_1") (pintype "passive"))
      (node (ref "U11") (pin "8") (pinfunction "VREF_8") (pintype "output"))
    )
    (net (code "82") (name "SPDIF_OUT") (class "Default")
      (node (ref "J5") (pin "P$1") (pinfunction "1_P$1") (pintype "passive"))
      (node (ref "R30") (pin "1") (pinfunction "1_1") (pintype "passive"))
      (node (ref "R31") (pin "2") (pinfunction "2_2") (pintype "passive"))
    )
    (net (code "83") (name "SPDIF_RST") (class "Default")
      (node (ref "U7") (pin "62") (pinfunction "PMD2/RE2_62") (pintype "bidirectional"))
      (node (ref "U9") (pin "15") (pinfunction "RST_15") (pintype "bidirectional"))
    )
    (net (code "84") (name "SPKR_OUT_L") (class "Default")
      (node (ref "C55") (pin "1") (pinfunction "1_1") (pintype "passive"))
      (node (ref "J2") (pin "1") (pinfunction "1_1") (pintype "bidirectional"))
      (node (ref "R32") (pin "2") (pinfunction "2_2") (pintype "passive"))
    )
    (net (code "85") (name "SPKR_OUT_R") (class "Default")
      (node (ref "C56") (pin "1") (pinfunction "1_1") (pintype "passive"))
      (node (ref "J2") (pin "4") (pinfunction "4_4") (pintype "bidirectional"))
      (node (ref "R33") (pin "2") (pinfunction "2_2") (pintype "passive"))
    )
    (net (code "86") (name "SYS_DTR") (class "Default")
      (node (ref "U3") (pin "1") (pinfunction "~{DTR}_1") (pintype "bidirectional"))
      (node (ref "U7") (pin "52") (pinfunction "RP25/PMWR/PMENB/RD4_52") (pintype "bidirectional"))
    )
    (net (code "87") (name "SYS_URX") (class "Default")
      (node (ref "U3") (pin "4") (pinfunction "RXD_4") (pintype "bidirectional"))
      (node (ref "U7") (pin "49") (pinfunction "RP24/U5TX/ICM4/RD1_49") (pintype "bidirectional"))
    )
    (net (code "88") (name "SYS_USB_DN") (class "Default")
      (node (ref "J6") (pin "2") (pinfunction "D-_2") (pintype "bidirectional"))
      (node (ref "U3") (pin "12") (pinfunction "USBDM_12") (pintype "bidirectional"))
    )
    (net (code "89") (name "SYS_USB_DP") (class "Default")
      (node (ref "J6") (pin "3") (pinfunction "D+_3") (pintype "bidirectional"))
      (node (ref "U3") (pin "11") (pinfunction "USBDP_11") (pintype "bidirectional"))
    )
    (net (code "90") (name "SYS_UTX") (class "Default")
      (node (ref "U3") (pin "20") (pinfunction "TXD_20") (pintype "bidirectional"))
      (node (ref "U7") (pin "50") (pinfunction "RP23/PMACK1/RD2_50") (pintype "bidirectional"))
    )
    (net (code "91") (name "TEL_AMP_SHDN") (class "Default")
      (node (ref "U11") (pin "12") (pinfunction "SHDN_12") (pintype "input"))
      (node (ref "U7") (pin "63") (pinfunction "CTED9/PMD3/RE3_63") (pintype "bidirectional"))
    )
    (net (code "92") (name "TEL_MIC_L_OUT") (class "Default")
      (node (ref "C40") (pin "2") (pinfunction "2_2") (pintype "passive"))
      (node (ref "J3") (pin "3") (pinfunction "3_3") (pintype "bidirectional"))
      (node (ref "R28") (pin "2") (pinfunction "2_2") (pintype "passive"))
    )
    (net (code "93") (name "TEL_MUTE_IO") (class "Default")
      (node (ref "J3") (pin "6") (pinfunction "6_6") (pintype "bidirectional"))
      (node (ref "Q1") (pin "3") (pinfunction "D_3") (pintype "bidirectional"))
    )
    (net (code "94") (name "TEL_ON_IO") (class "Default")
      (node (ref "J3") (pin "5") (pinfunction "5_5") (pintype "bidirectional"))
      (node (ref "R7") (pin "2") (pinfunction "2_2") (pintype "passive"))
    )
    (net (code "95") (name "TEL_OUT_L+") (class "Default")
      (node (ref "C44") (pin "1") (pinfunction "1_1") (pintype "passive"))
      (node (ref "FB2") (pin "2") (pinfunction "2_2") (pintype "bidirectional"))
      (node (ref "J3") (pin "1") (pinfunction "1_1") (pintype "bidirectional"))
    )
    (net (code "96") (name "TEL_OUT_L-") (class "Default")
      (node (ref "C43") (pin "1") (pinfunction "1_1") (pintype "passive"))
      (node (ref "FB1") (pin "2") (pinfunction "2_2") (pintype "bidirectional"))
      (node (ref "J3") (pin "2") (pinfunction "2_2") (pintype "bidirectional"))
    )
    (net (code "97") (name "USB_3V3") (class "Default")
      (node (ref "C26") (pin "1") (pinfunction "1_1") (pintype "passive"))
      (node (ref "RX") (pin "+") (pinfunction "A_+") (pintype "passive"))
      (node (ref "TX") (pin "+") (pinfunction "A_+") (pintype "passive"))
      (node (ref "U3") (pin "13") (pinfunction "3V3OUT_13") (pintype "bidirectional"))
      (node (ref "U3") (pin "14") (pinfunction "~{RESET}_14") (pintype "bidirectional"))
      (node (ref "U3") (pin "3") (pinfunction "VCCIO_3") (pintype "bidirectional"))
    )
    (net (code "98") (name "USB_5V") (class "Default")
      (node (ref "D3") (pin "A") (pinfunction "A_A") (pintype "passive"))
      (node (ref "J6") (pin "1") (pinfunction "VBUS_1") (pintype "power_in"))
    )
    (net (code "99") (name "VBAT") (class "Default")
      (node (ref "D1") (pin "A") (pinfunction "A_A") (pintype "passive"))
      (node (ref "J1") (pin "2") (pinfunction "2_2") (pintype "passive"))
    )
    (net (code "100") (name "VBAT_FLT") (class "Default")
      (node (ref "F1") (pin "OUT") (pinfunction "IN_OUT") (pintype "bidirectional"))
      (node (ref "L1") (pin "1") (pinfunction "1_1") (pintype "passive"))
    )
    (net (code "101") (name "VIN") (class "Default")
      (node (ref "C10") (pin "1") (pinfunction "1_1") (pintype "passive"))
      (node (ref "C11") (pin "1") (pinfunction "1_1") (pintype "passive"))
      (node (ref "C22") (pin "1") (pinfunction "1_1") (pintype "passive"))
      (node (ref "C3") (pin "1") (pinfunction "1_1") (pintype "passive"))
      (node (ref "C4") (pin "1") (pinfunction "1_1") (pintype "passive"))
      (node (ref "C9") (pin "1") (pinfunction "1_1") (pintype "passive"))
      (node (ref "L1") (pin "4") (pinfunction "4_4") (pintype "passive"))
      (node (ref "SW1") (pin "2") (pinfunction "2_2") (pintype "bidirectional"))
      (node (ref "U1") (pin "2") (pinfunction "IN_2") (pintype "bidirectional"))
      (node (ref "U2") (pin "1") (pinfunction "VS_1") (pintype "power_in"))
      (node (ref "U4") (pin "1") (pinfunction "VIN_1") (pintype "power_in"))
    )
    (net (code "102") (name "unconnected-(J2-Pad3)") (class "Default")
      (node (ref "J2") (pin "3") (pinfunction "3_3") (pintype "bidirectional"))
    )
    (net (code "103") (name "unconnected-(J2-Pad6)") (class "Default")
      (node (ref "J2") (pin "6") (pinfunction "6_6") (pintype "bidirectional"))
    )
    (net (code "104") (name "unconnected-(J4-RING-Pad3)") (class "Default")
      (node (ref "J4") (pin "3") (pinfunction "RING_3") (pintype "passive"))
    )
    (net (code "105") (name "unconnected-(J6-ID-Pad4)") (class "Default")
      (node (ref "J6") (pin "4") (pinfunction "ID_4") (pintype "bidirectional"))
    )
    (net (code "106") (name "unconnected-(J8-Pad6)") (class "Default")
      (node (ref "J8") (pin "6") (pinfunction "6_6") (pintype "bidirectional"))
    )
    (net (code "107") (name "unconnected-(U2-RESET-Pad14)") (class "Default")
      (node (ref "U2") (pin "14") (pinfunction "RESET_14") (pintype "output"))
    )
    (net (code "108") (name "unconnected-(U2-SENSE-Pad15)") (class "Default")
      (node (ref "U2") (pin "15") (pinfunction "SENSE_15") (pintype "bidirectional"))
    )
    (net (code "109") (name "unconnected-(U2-SO-Pad8)") (class "Default")
      (node (ref "U2") (pin "8") (pinfunction "SO_8") (pintype "output"))
    )
    (net (code "110") (name "unconnected-(U3-CBUS0-Pad18)") (class "Default")
      (node (ref "U3") (pin "18") (pinfunction "CBUS0_18") (pintype "bidirectional"))
    )
    (net (code "111") (name "unconnected-(U3-CBUS3-Pad19)") (class "Default")
      (node (ref "U3") (pin "19") (pinfunction "CBUS3_19") (pintype "bidirectional"))
    )
    (net (code "112") (name "unconnected-(U3-~{CTS}-Pad9)") (class "Default")
      (node (ref "U3") (pin "9") (pinfunction "~{CTS}_9") (pintype "bidirectional"))
    )
    (net (code "113") (name "unconnected-(U3-~{DCD}-Pad8)") (class "Default")
      (node (ref "U3") (pin "8") (pinfunction "~{DCD}_8") (pintype "bidirectional"))
    )
    (net (code "114") (name "unconnected-(U3-~{DSR}-Pad7)") (class "Default")
      (node (ref "U3") (pin "7") (pinfunction "~{DSR}_7") (pintype "bidirectional"))
    )
    (net (code "115") (name "unconnected-(U3-~{RI}-Pad5)") (class "Default")
      (node (ref "U3") (pin "5") (pinfunction "~{RI}_5") (pintype "bidirectional"))
    )
    (net (code "116") (name "unconnected-(U3-~{RTS}-Pad2)") (class "Default")
      (node (ref "U3") (pin "2") (pinfunction "~{RTS}_2") (pintype "bidirectional"))
    )
    (net (code "117") (name "unconnected-(U4-NC-Pad3)") (class "Default")
      (node (ref "U4") (pin "3") (pinfunction "NC_3") (pintype "no_connect"))
    )
    (net (code "118") (name "unconnected-(U5-NC-Pad4)") (class "Default")
      (node (ref "U5") (pin "4") (pinfunction "NC_4") (pintype "no_connect"))
    )
    (net (code "119") (name "unconnected-(U7-AN2{slash}CTCMP{slash}C2INB{slash}RP13{slash}CTED13{slash}RB2-Pad14)") (class "Default")
      (node (ref "U7") (pin "14") (pinfunction "AN2/CTCMP/C2INB/RP13/CTED13/RB2_14") (pintype "bidirectional"))
    )
    (net (code "120") (name "unconnected-(U7-AN3{slash}C2INA{slash}RB3-Pad13)") (class "Default")
      (node (ref "U7") (pin "13") (pinfunction "AN3/C2INA/RB3_13") (pintype "bidirectional"))
    )
    (net (code "121") (name "unconnected-(U7-AN8{slash}RP8{slash}PWRGT{slash}RB8-Pad21)") (class "Default")
      (node (ref "U7") (pin "21") (pinfunction "AN8/RP8/PWRGT/RB8_21") (pintype "bidirectional"))
    )
    (net (code "122") (name "unconnected-(U7-AN9{slash}TMPR{slash}RP9{slash}T1CK{slash}PMA7{slash}RB9-Pad22)") (class "Default")
      (node (ref "U7") (pin "22") (pinfunction "AN9/TMPR/RP9/T1CK/PMA7/RB9_22") (pintype "bidirectional"))
    )
    (net (code "123") (name "unconnected-(U7-AN14{slash}RP14{slash}CTED5{slash}CTPLS{slash}PMA1{slash}PMALH{slash}RB14-Pad29)") (class "Default")
      (node (ref "U7") (pin "29") (pinfunction "AN14/RP14/CTED5/CTPLS/PMA1/PMALH/RB14_29") (pintype "bidirectional"))
    )
    (net (code "124") (name "unconnected-(U7-AN15{slash}RP29{slash}CTED6{slash}PMA0{slash}PMALL{slash}RB15-Pad30)") (class "Default")
      (node (ref "U7") (pin "30") (pinfunction "AN15/RP29/CTED6/PMA0/PMALL/RB15_30") (pintype "bidirectional"))
    )
    (net (code "125") (name "unconnected-(U7-C1INC{slash}C2INC{slash}C3INC{slash}RP27{slash}OCM2B{slash}PMA2{slash}PMALU{slash}RG9-Pad8)") (class "Default")
      (node (ref "U7") (pin "8") (pinfunction "C1INC/C2INC/C3INC/RP27/OCM2B/PMA2/PMALU/RG9_8") (pintype "bidirectional"))
    )
    (net (code "126") (name "unconnected-(U7-C3INA{slash}U5RTS{slash}U5BCLK{slash}OC5{slash}RD7-Pad55)") (class "Default")
      (node (ref "U7") (pin "55") (pinfunction "C3INA/U5RTS/U5BCLK/OC5/RD7_55") (pintype "bidirectional"))
    )
    (net (code "127") (name "unconnected-(U7-C3INB{slash}U5RX{slash}OC4{slash}RD6-Pad54)") (class "Default")
      (node (ref "U7") (pin "54") (pinfunction "C3INB/U5RX/OC4/RD6_54") (pintype "bidirectional"))
    )
    (net (code "128") (name "unconnected-(U7-HLVDIN{slash}CTED8{slash}PMD4{slash}RE4-Pad64)") (class "Default")
      (node (ref "U7") (pin "64") (pinfunction "HLVDIN/CTED8/PMD4/RE4_64") (pintype "bidirectional"))
    )
    (net (code "129") (name "unconnected-(U7-INT0{slash}RF6-Pad35)") (class "Default")
      (node (ref "U7") (pin "35") (pinfunction "INT0/RF6_35") (pintype "bidirectional"))
    )
    (net (code "130") (name "unconnected-(U7-N{slash}C-Pad57)") (class "Default")
      (node (ref "U7") (pin "57") (pinfunction "N/C_57") (pintype "no_connect"))
    )
    (net (code "131") (name "unconnected-(U7-OSCI{slash}CLKI{slash}RC12-Pad39)") (class "Default")
      (node (ref "U7") (pin "39") (pinfunction "OSCI/CLKI/RC12_39") (pintype "bidirectional"))
    )
    (net (code "132") (name "unconnected-(U7-OSCO{slash}CLKO{slash}RC15-Pad40)") (class "Default")
      (node (ref "U7") (pin "40") (pinfunction "OSCO/CLKO/RC15_40") (pintype "bidirectional"))
    )
    (net (code "133") (name "unconnected-(U7-PGEC2{slash}AN6{slash}RP6{slash}RB6-Pad17)") (class "Default")
      (node (ref "U7") (pin "17") (pinfunction "PGEC2/AN6/RP6/RB6_17") (pintype "bidirectional"))
    )
    (net (code "134") (name "unconnected-(U7-PGEC3{slash}AN5{slash}C1INA{slash}RP18{slash}ICM3{slash}OCM3A{slash}RB5-Pad11)") (class "Default")
      (node (ref "U7") (pin "11") (pinfunction "PGEC3/AN5/C1INA/RP18/ICM3/OCM3A/RB5_11") (pintype "bidirectional"))
    )
    (net (code "135") (name "unconnected-(U7-PGED2{slash}AN7{slash}RP7{slash}U6TX{slash}RB7-Pad18)") (class "Default")
      (node (ref "U7") (pin "18") (pinfunction "PGED2/AN7/RP7/U6TX/RB7_18") (pintype "bidirectional"))
    )
    (net (code "136") (name "unconnected-(U7-PGED3{slash}AN4{slash}C1INB{slash}RP28{slash}OCM3B{slash}RB4-Pad12)") (class "Default")
      (node (ref "U7") (pin "12") (pinfunction "PGED3/AN4/C1INB/RP28/OCM3B/RB4_12") (pintype "bidirectional"))
    )
    (net (code "137") (name "unconnected-(U7-RP22{slash}ICM7{slash}PMBE0{slash}RD3-Pad51)") (class "Default")
      (node (ref "U7") (pin "51") (pinfunction "RP22/ICM7/PMBE0/RD3_51") (pintype "bidirectional"))
    )
    (net (code "138") (name "unconnected-(U7-SCL1{slash}RG2-Pad37)") (class "Default")
      (node (ref "U7") (pin "37") (pinfunction "SCL1/RG2_37") (pintype "bidirectional"))
    )
    (net (code "139") (name "unconnected-(U7-SDA1{slash}RG3-Pad36)") (class "Default")
      (node (ref "U7") (pin "36") (pinfunction "SDA1/RG3_36") (pintype "bidirectional"))
    )
    (net (code "140") (name "unconnected-(U7-SOSCI{slash}C3IND{slash}RC13-Pad47)") (class "Default")
      (node (ref "U7") (pin "47") (pinfunction "SOSCI/C3IND/RC13_47") (pintype "bidirectional"))
    )
    (net (code "141") (name "unconnected-(U7-SOSCO{slash}C3INC{slash}RPI37{slash}PWRLCLK{slash}RC14-Pad48)") (class "Default")
      (node (ref "U7") (pin "48") (pinfunction "SOSCO/C3INC/RPI37/PWRLCLK/RC14_48") (pintype "bidirectional"))
    )
    (net (code "142") (name "unconnected-(U7-TCK{slash}AN12{slash}U6RX{slash}CTED2{slash}PMA11{slash}RB12-Pad27)") (class "Default")
      (node (ref "U7") (pin "27") (pinfunction "TCK/AN12/U6RX/CTED2/PMA11/RB12_27") (pintype "bidirectional"))
    )
    (net (code "143") (name "unconnected-(U7-TDI{slash}AN13{slash}CTED1{slash}PMA10{slash}RB13-Pad28)") (class "Default")
      (node (ref "U7") (pin "28") (pinfunction "TDI/AN13/CTED1/PMA10/RB13_28") (pintype "bidirectional"))
    )
    (net (code "144") (name "unconnected-(U7-TDO{slash}AN11{slash}REFI{slash}PMA12{slash}RB11-Pad24)") (class "Default")
      (node (ref "U7") (pin "24") (pinfunction "TDO/AN11/REFI/PMA12/RB11_24") (pintype "bidirectional"))
    )
    (net (code "145") (name "unconnected-(U7-TMS{slash}CVREF{slash}AN10{slash}PMA13{slash}RB10-Pad23)") (class "Default")
      (node (ref "U7") (pin "23") (pinfunction "TMS/CVREF/AN10/PMA13/RB10_23") (pintype "bidirectional"))
    )
    (net (code "146") (name "unconnected-(U8-ADAP_IN-Pad22)") (class "Default")
      (node (ref "U8") (pin "22") (pinfunction "ADAP_IN_22") (pintype "bidirectional"))
    )
    (net (code "147") (name "unconnected-(U8-AIL-Pad12)") (class "Default")
      (node (ref "U8") (pin "12") (pinfunction "AIL_12") (pintype "bidirectional"))
    )
    (net (code "148") (name "unconnected-(U8-AIR-Pad11)") (class "Default")
      (node (ref "U8") (pin "11") (pinfunction "AIR_11") (pintype "bidirectional"))
    )
    (net (code "149") (name "unconnected-(U8-AOHPL-Pad8)") (class "Default")
      (node (ref "U8") (pin "8") (pinfunction "AOHPL_8") (pintype "bidirectional"))
    )
    (net (code "150") (name "unconnected-(U8-AOHPM-Pad7)") (class "Default")
      (node (ref "U8") (pin "7") (pinfunction "AOHPM_7") (pintype "bidirectional"))
    )
    (net (code "151") (name "unconnected-(U8-AOHPR-Pad6)") (class "Default")
      (node (ref "U8") (pin "6") (pinfunction "AOHPR_6") (pintype "bidirectional"))
    )
    (net (code "152") (name "unconnected-(U8-DM-Pad36)") (class "Default")
      (node (ref "U8") (pin "36") (pinfunction "DM_36") (pintype "bidirectional"))
    )
    (net (code "153") (name "unconnected-(U8-DMIC1_L-Pad19)") (class "Default")
      (node (ref "U8") (pin "19") (pinfunction "DMIC1_L_19") (pintype "bidirectional"))
    )
    (net (code "154") (name "unconnected-(U8-DMIC1_R-Pad18)") (class "Default")
      (node (ref "U8") (pin "18") (pinfunction "DMIC1_R_18") (pintype "bidirectional"))
    )
    (net (code "155") (name "unconnected-(U8-DMIC_CLK-Pad17)") (class "Default")
      (node (ref "U8") (pin "17") (pinfunction "DMIC_CLK_17") (pintype "bidirectional"))
    )
    (net (code "156") (name "unconnected-(U8-DP-Pad37)") (class "Default")
      (node (ref "U8") (pin "37") (pinfunction "DP_37") (pintype "bidirectional"))
    )
    (net (code "157") (name "unconnected-(U8-DR1-Pad1)") (class "Default")
      (node (ref "U8") (pin "1") (pinfunction "DR1_1") (pintype "bidirectional"))
    )
    (net (code "158") (name "unconnected-(U8-LED1-Pad32)") (class "Default")
      (node (ref "U8") (pin "32") (pinfunction "LED1_32") (pintype "bidirectional"))
    )
    (net (code "159") (name "unconnected-(U8-LED2-Pad34)") (class "Default")
      (node (ref "U8") (pin "34") (pinfunction "LED2_34") (pintype "bidirectional"))
    )
    (net (code "160") (name "unconnected-(U8-MICN2-Pad9)") (class "Default")
      (node (ref "U8") (pin "9") (pinfunction "MICN2_9") (pintype "bidirectional"))
    )
    (net (code "161") (name "unconnected-(U8-MICP2-Pad10)") (class "Default")
      (node (ref "U8") (pin "10") (pinfunction "MICP2_10") (pintype "bidirectional"))
    )
    (net (code "162") (name "unconnected-(U8-P0_0{slash}UART_TX_IND-Pad49)") (class "Default")
      (node (ref "U8") (pin "49") (pinfunction "P0_0/UART_TX_IND_49") (pintype "bidirectional"))
    )
    (net (code "163") (name "unconnected-(U8-P0_1-Pad44)") (class "Default")
      (node (ref "U8") (pin "44") (pinfunction "P0_1_44") (pintype "bidirectional"))
    )
    (net (code "164") (name "unconnected-(U8-P0_2-Pad33)") (class "Default")
      (node (ref "U8") (pin "33") (pinfunction "P0_2_33") (pintype "bidirectional"))
    )
    (net (code "165") (name "unconnected-(U8-P0_3-Pad38)") (class "Default")
      (node (ref "U8") (pin "38") (pinfunction "P0_3_38") (pintype "bidirectional"))
    )
    (net (code "166") (name "unconnected-(U8-P0_5-Pad40)") (class "Default")
      (node (ref "U8") (pin "40") (pinfunction "P0_5_40") (pintype "bidirectional"))
    )
    (net (code "167") (name "unconnected-(U8-P0_6-Pad35)") (class "Default")
      (node (ref "U8") (pin "35") (pinfunction "P0_6_35") (pintype "bidirectional"))
    )
    (net (code "168") (name "unconnected-(U8-P0_7-Pad45)") (class "Default")
      (node (ref "U8") (pin "45") (pinfunction "P0_7_45") (pintype "bidirectional"))
    )
    (net (code "169") (name "unconnected-(U8-P1_2{slash}TDI_CPU{slash}SCL-Pad46)") (class "Default")
      (node (ref "U8") (pin "46") (pinfunction "P1_2/TDI_CPU/SCL_46") (pintype "bidirectional"))
    )
    (net (code "170") (name "unconnected-(U8-P1_3{slash}TCK_CPU{slash}SDA-Pad47)") (class "Default")
      (node (ref "U8") (pin "47") (pinfunction "P1_3/TCK_CPU/SDA_47") (pintype "bidirectional"))
    )
    (net (code "171") (name "unconnected-(U8-P1_6{slash}PWM1-Pad41)") (class "Default")
      (node (ref "U8") (pin "41") (pinfunction "P1_6/PWM1_41") (pintype "bidirectional"))
    )
    (net (code "172") (name "unconnected-(U8-P2_3-Pad42)") (class "Default")
      (node (ref "U8") (pin "42") (pinfunction "P2_3_42") (pintype "bidirectional"))
    )
    (net (code "173") (name "unconnected-(U8-P2_6-Pad21)") (class "Default")
      (node (ref "U8") (pin "21") (pinfunction "P2_6_21") (pintype "bidirectional"))
    )
    (net (code "174") (name "unconnected-(U8-P2_7-Pad39)") (class "Default")
      (node (ref "U8") (pin "39") (pinfunction "P2_7_39") (pintype "bidirectional"))
    )
    (net (code "175") (name "unconnected-(U8-P3_2-Pad20)") (class "Default")
      (node (ref "U8") (pin "20") (pinfunction "P3_2_20") (pintype "bidirectional"))
    )
    (net (code "176") (name "unconnected-(U8-P3_7{slash}UART_CTS-Pad48)") (class "Default")
      (node (ref "U8") (pin "48") (pinfunction "P3_7/UART_CTS_48") (pintype "bidirectional"))
    )
    (net (code "177") (name "unconnected-(U8-SK2_KEY_AD-Pad28)") (class "Default")
      (node (ref "U8") (pin "28") (pinfunction "SK2_KEY_AD_28") (pintype "bidirectional"))
    )
    (net (code "178") (name "unconnected-(U8-SKI1_AMB_DET-Pad27)") (class "Default")
      (node (ref "U8") (pin "27") (pinfunction "SKI1_AMB_DET_27") (pintype "bidirectional"))
    )
    (net (code "179") (name "unconnected-(U9-BLS-Pad25)") (class "Default")
      (node (ref "U9") (pin "25") (pinfunction "BLS_25") (pintype "bidirectional"))
    )
    (net (code "180") (name "unconnected-(U9-TX--Pad17)") (class "Default")
      (node (ref "U9") (pin "17") (pinfunction "TX-_17") (pintype "bidirectional"))
    )
    (net (code "181") (name "unconnected-(U10-GPIO3{slash}AGNS-Pad15)") (class "Default")
      (node (ref "U10") (pin "15") (pinfunction "GPIO3/AGNS_15") (pintype "bidirectional"))
    )
    (net (code "182") (name "unconnected-(U10-GPIO4{slash}MAST-Pad14)") (class "Default")
      (node (ref "U10") (pin "14") (pinfunction "GPIO4/MAST_14") (pintype "bidirectional"))
    )
    (net (code "183") (name "unconnected-(U10-GPIO5{slash}ATT0-Pad13)") (class "Default")
      (node (ref "U10") (pin "13") (pinfunction "GPIO5/ATT0_13") (pintype "bidirectional"))
    )
    (net (code "184") (name "unconnected-(U10-GPIO6{slash}FLT-Pad19)") (class "Default")
      (node (ref "U10") (pin "19") (pinfunction "GPIO6/FLT_19") (pintype "input"))
    )
    (net (code "185") (name "unconnected-(U11-MUTE-Pad5)") (class "Default")
      (node (ref "U11") (pin "5") (pinfunction "MUTE_5") (pintype "input"))
    )
    (net (code "186") (name "unconnected-(U11-OUT_R+-Pad16)") (class "Default")
      (node (ref "U11") (pin "16") (pinfunction "OUT_R+_16") (pintype "output"))
    )
    (net (code "187") (name "unconnected-(U11-OUT_R--Pad14)") (class "Default")
      (node (ref "U11") (pin "14") (pinfunction "OUT_R-_14") (pintype "output"))
    )
  )
)
